# 20240610.net
KiCad netlist of a schematic drawn in EAGLE
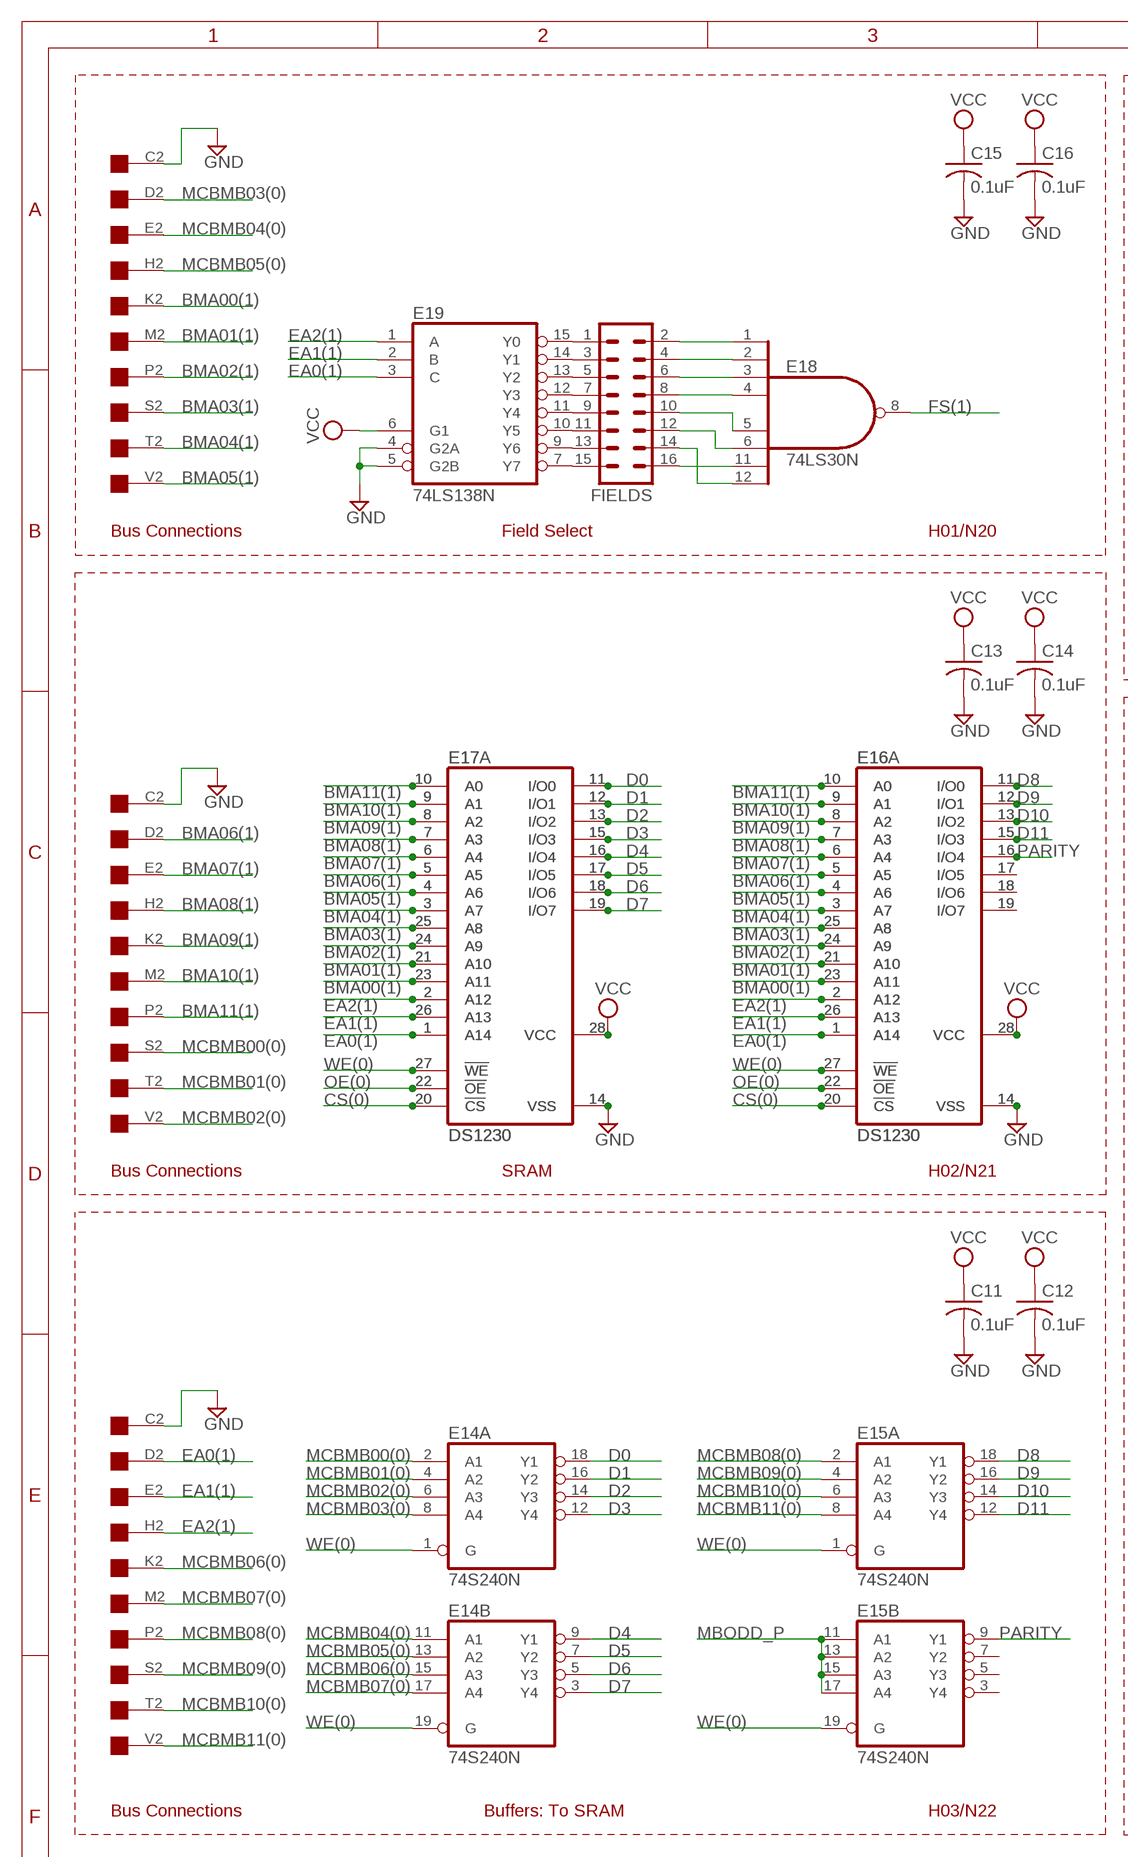
[diagram p0: schematic, sheet 1, part 1 of 2]
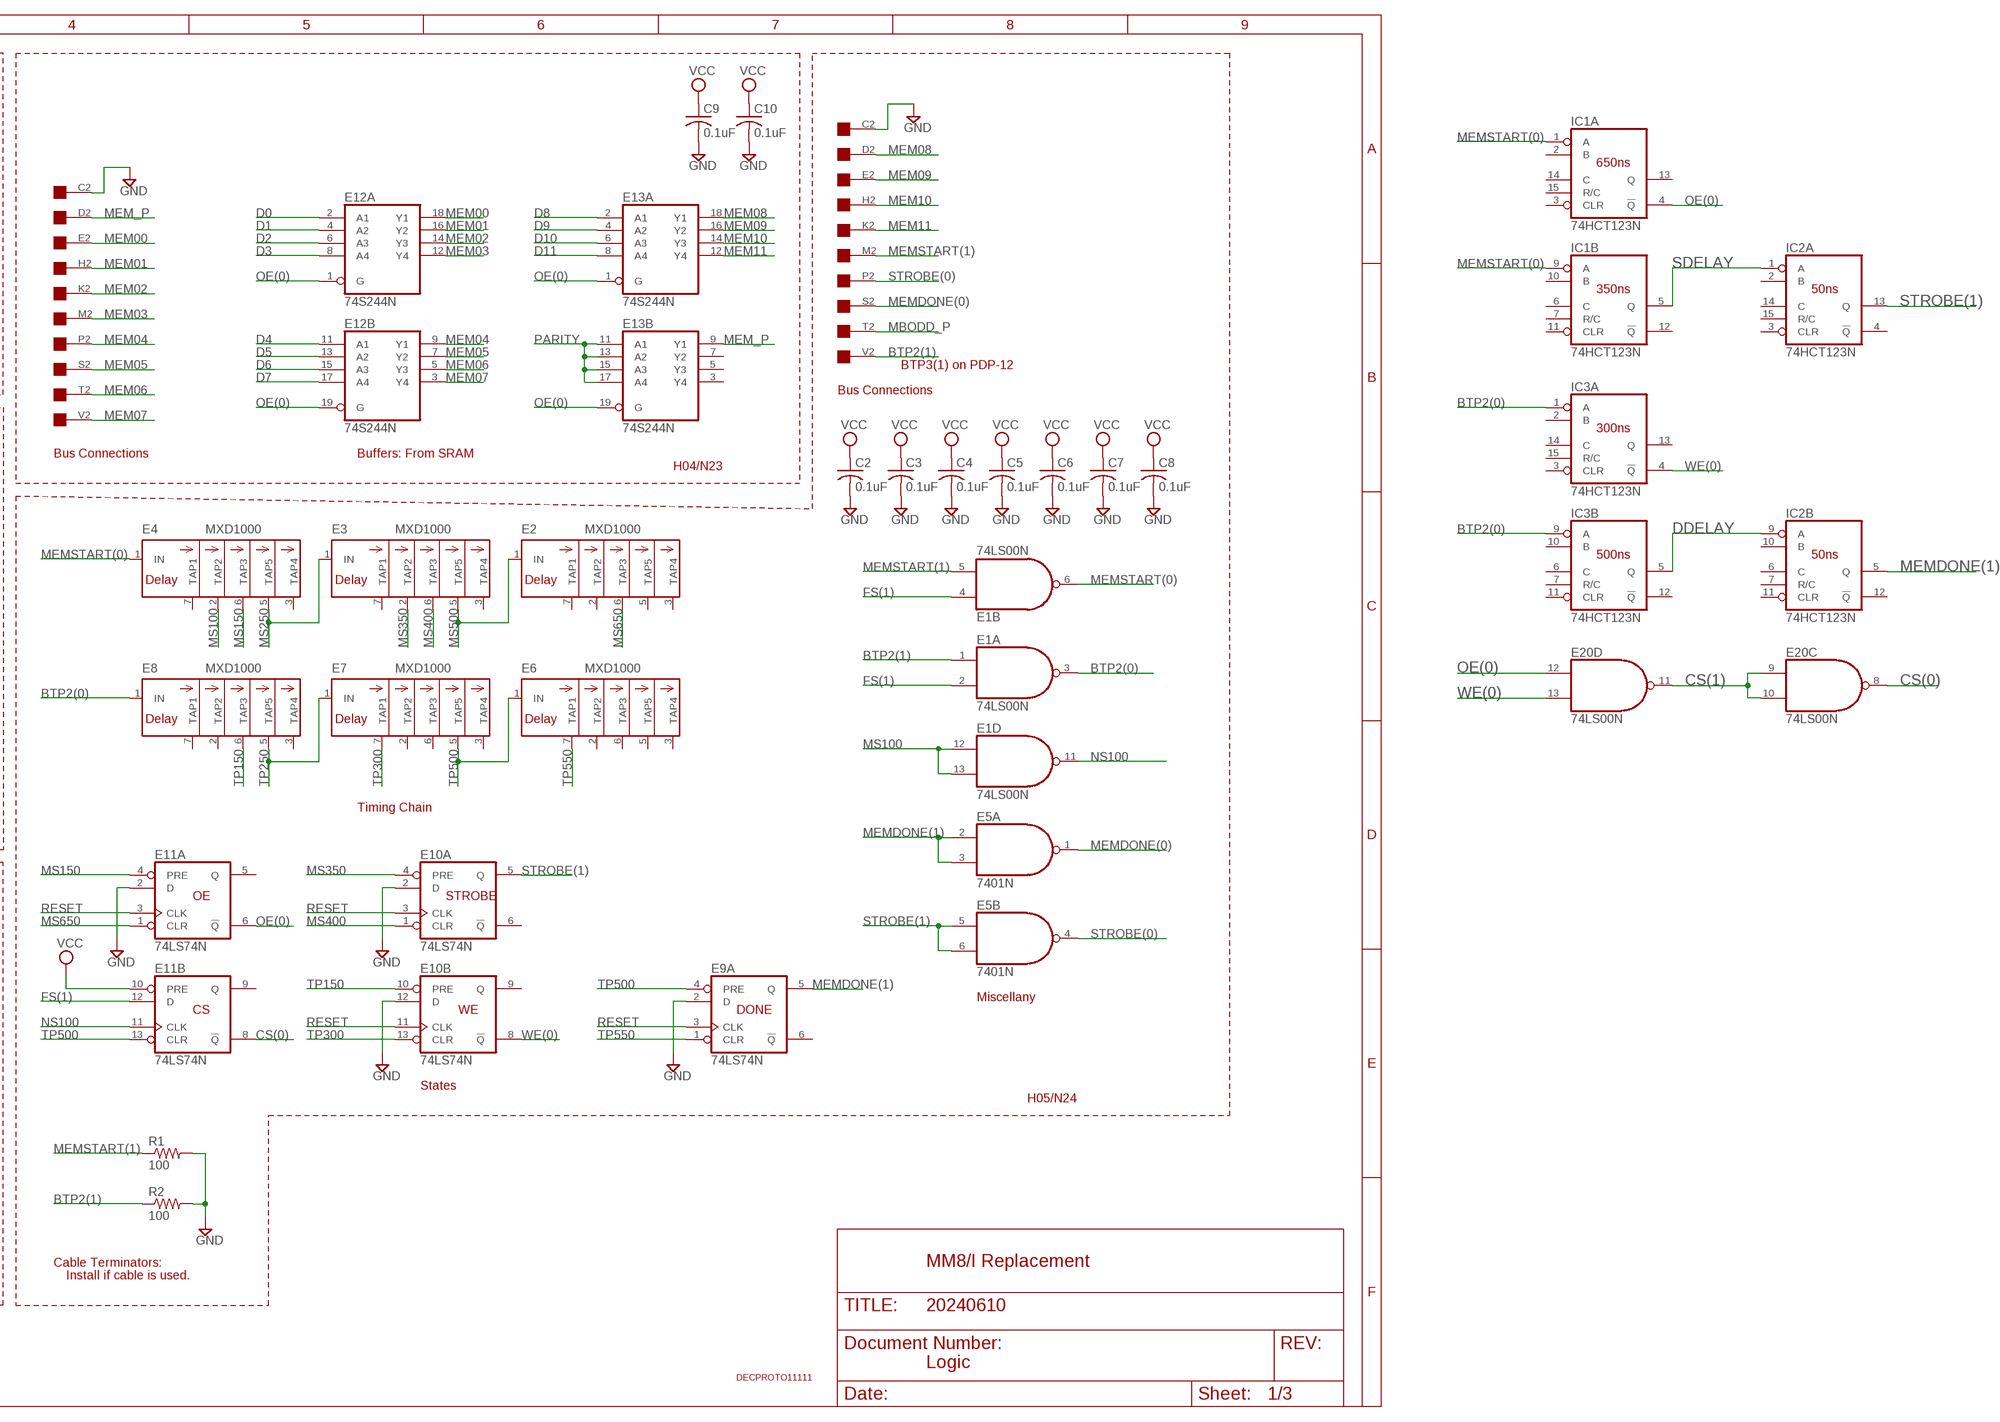
[diagram p1: schematic, sheet 1, part 2 of 2]
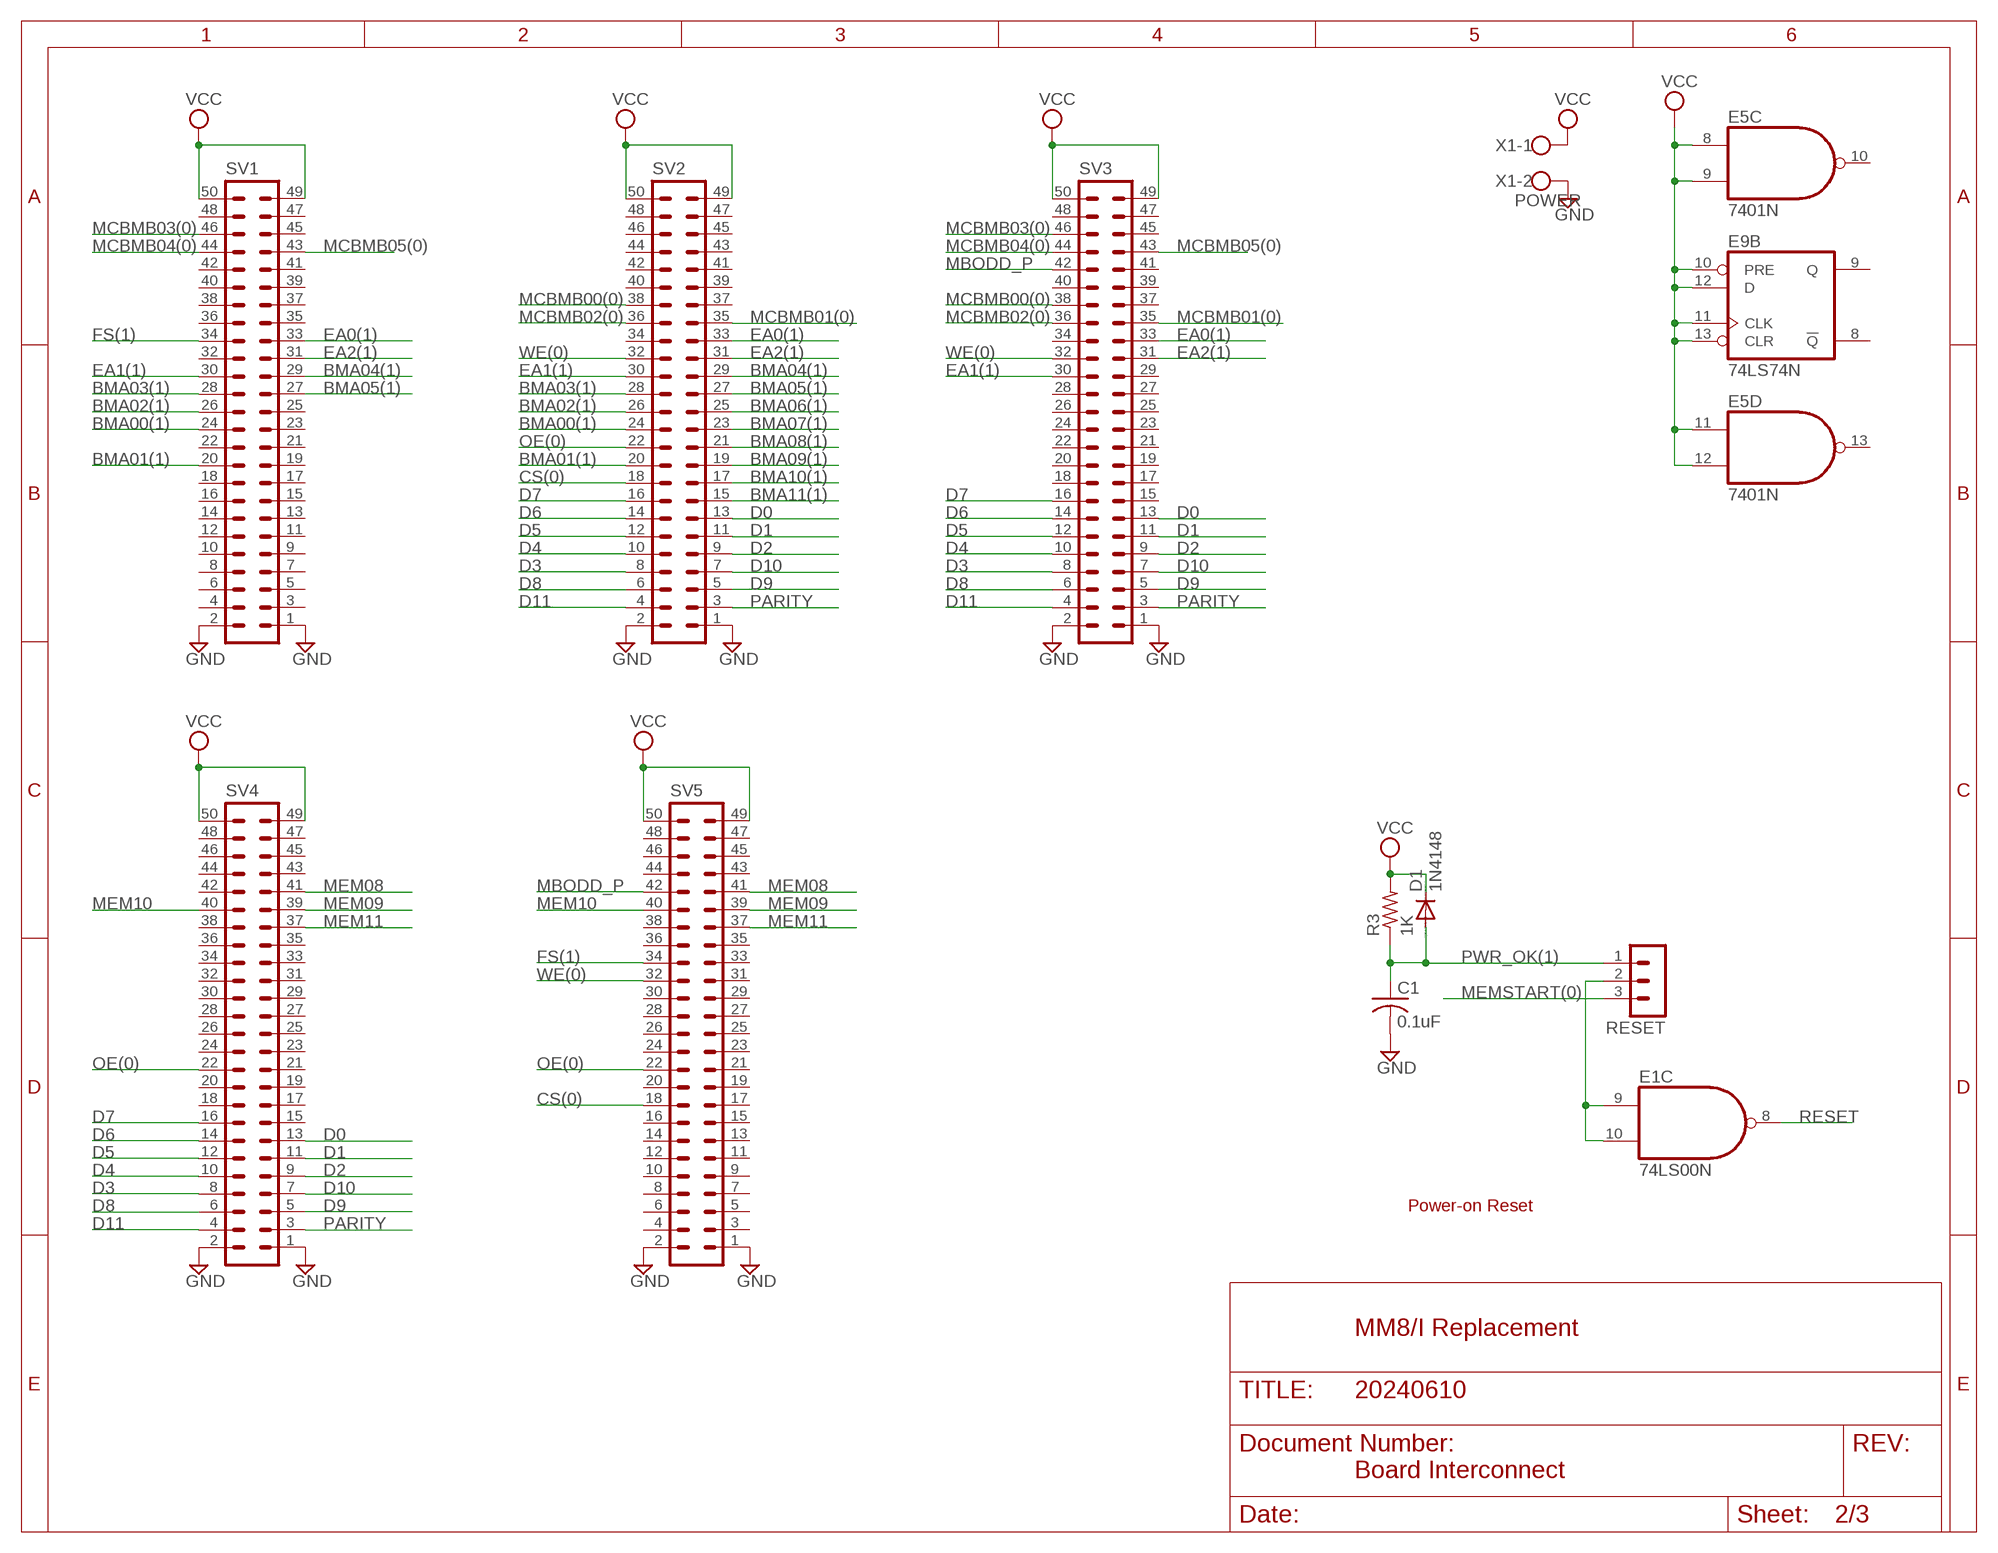
[diagram p2: schematic, sheet 2]
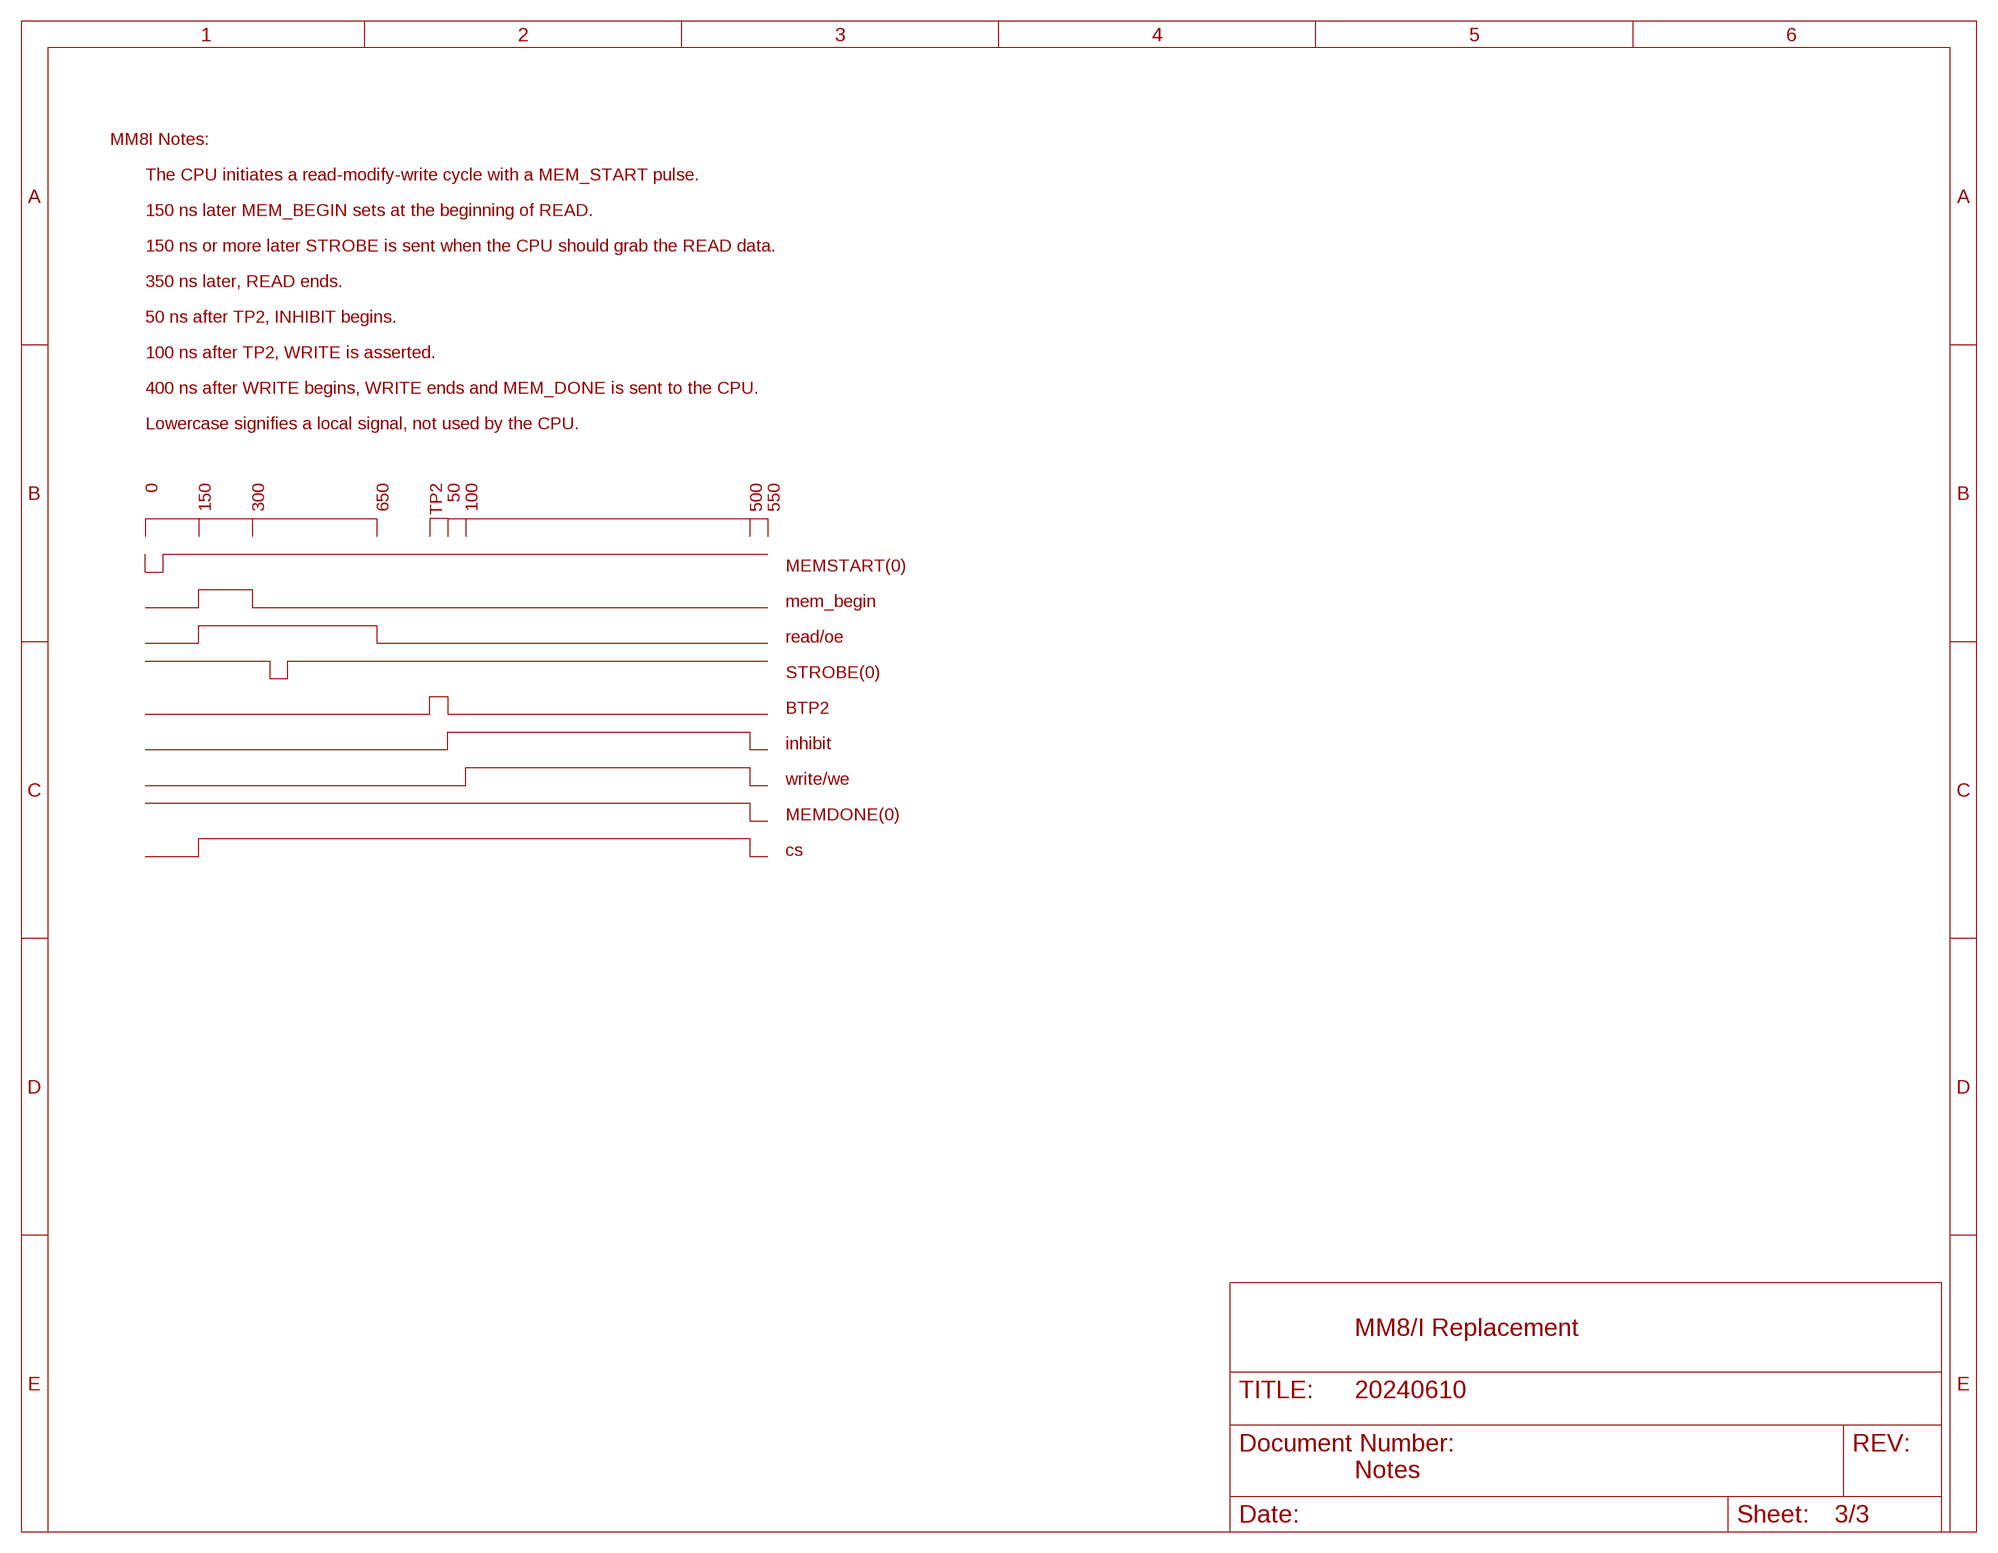
[diagram p3: schematic, sheet 3]

(export (version "E")
  (design (tool "Eeschema 10.0.6"))
  (components
    (comp (ref "C1")
      (value "0.1uF")
      (footprint "eagle-import:C050-025X075")
      (libsource (lib "eagle-import") (part "C-US050-025X075"))
    )
    (comp (ref "D1")
      (value "1N4148")
      (footprint "eagle-import:DO35-10")
      (libsource (lib "eagle-import") (part "1N4148DO35-10"))
    )
    (comp (ref "E1")
      (value "74LS00N")
      (footprint "eagle-import:DIL14")
      (libsource (lib "eagle-import") (part "7400NLS"))
    )
    (comp (ref "E5")
      (value "7401N")
      (footprint "eagle-import:DIL14")
      (libsource (lib "eagle-import") (part "7401NLS"))
    )
    (comp (ref "E9")
      (value "74LS74N")
      (footprint "eagle-import:DIL14")
      (libsource (lib "eagle-import") (part "7474NLS"))
    )
    (comp (ref "R3")
      (value "1K")
      (footprint "eagle-import:0207_10")
      (libsource (lib "eagle-import") (part "R-US_0207/10"))
    )
    (comp (ref "RESET")
      (value "MA03-1")
      (footprint "eagle-import:MA03-1")
      (libsource (lib "eagle-import") (part "MA03-1"))
    )
    (comp (ref "SV1")
      (value "ML50L")
      (footprint "eagle-import:ML50L")
      (libsource (lib "eagle-import") (part "ML50L"))
    )
    (comp (ref "SV2")
      (value "ML50L")
      (footprint "eagle-import:ML50L")
      (libsource (lib "eagle-import") (part "ML50L"))
    )
    (comp (ref "SV3")
      (value "ML50L")
      (footprint "eagle-import:ML50L")
      (libsource (lib "eagle-import") (part "ML50L"))
    )
    (comp (ref "SV4")
      (value "ML50L")
      (footprint "eagle-import:ML50L")
      (libsource (lib "eagle-import") (part "ML50L"))
    )
    (comp (ref "SV5")
      (value "ML50L")
      (footprint "eagle-import:ML50L")
      (libsource (lib "eagle-import") (part "ML50L"))
    )
    (comp (ref "X1")
      (value "POWER")
      (footprint "eagle-import:W237-102")
      (fields (field (name "MPN") "237-102"))
      (libsource (lib "eagle-import") (part "W237-102"))
    )
    (comp (ref "C2")
      (value "0.1uF")
      (footprint "eagle-import:C050-025X075")
      (libsource (lib "eagle-import") (part "C-US050-025X075"))
    )
    (comp (ref "C3")
      (value "0.1uF")
      (footprint "eagle-import:C050-025X075")
      (libsource (lib "eagle-import") (part "C-US050-025X075"))
    )
    (comp (ref "C4")
      (value "0.1uF")
      (footprint "eagle-import:C050-025X075")
      (libsource (lib "eagle-import") (part "C-US050-025X075"))
    )
    (comp (ref "C5")
      (value "0.1uF")
      (footprint "eagle-import:C050-025X075")
      (libsource (lib "eagle-import") (part "C-US050-025X075"))
    )
    (comp (ref "C6")
      (value "0.1uF")
      (footprint "eagle-import:C050-025X075")
      (libsource (lib "eagle-import") (part "C-US050-025X075"))
    )
    (comp (ref "C7")
      (value "0.1uF")
      (footprint "eagle-import:C050-025X075")
      (libsource (lib "eagle-import") (part "C-US050-025X075"))
    )
    (comp (ref "C8")
      (value "0.1uF")
      (footprint "eagle-import:C050-025X075")
      (libsource (lib "eagle-import") (part "C-US050-025X075"))
    )
    (comp (ref "C9")
      (value "0.1uF")
      (footprint "eagle-import:C050-025X075")
      (libsource (lib "eagle-import") (part "C-US050-025X075"))
    )
    (comp (ref "C10")
      (value "0.1uF")
      (footprint "eagle-import:C050-025X075")
      (libsource (lib "eagle-import") (part "C-US050-025X075"))
    )
    (comp (ref "C11")
      (value "0.1uF")
      (footprint "eagle-import:C050-025X075")
      (libsource (lib "eagle-import") (part "C-US050-025X075"))
    )
    (comp (ref "C12")
      (value "0.1uF")
      (footprint "eagle-import:C050-025X075")
      (libsource (lib "eagle-import") (part "C-US050-025X075"))
    )
    (comp (ref "C13")
      (value "0.1uF")
      (footprint "eagle-import:C050-025X075")
      (libsource (lib "eagle-import") (part "C-US050-025X075"))
    )
    (comp (ref "C14")
      (value "0.1uF")
      (footprint "eagle-import:C050-025X075")
      (libsource (lib "eagle-import") (part "C-US050-025X075"))
    )
    (comp (ref "C15")
      (value "0.1uF")
      (footprint "eagle-import:C050-025X075")
      (libsource (lib "eagle-import") (part "C-US050-025X075"))
    )
    (comp (ref "C16")
      (value "0.1uF")
      (footprint "eagle-import:C050-025X075")
      (libsource (lib "eagle-import") (part "C-US050-025X075"))
    )
    (comp (ref "E2")
      (value "MXD1000")
      (footprint "eagle-import:DIL08")
      (libsource (lib "eagle-import") (part "MXD1000"))
    )
    (comp (ref "E3")
      (value "MXD1000")
      (footprint "eagle-import:DIL08")
      (libsource (lib "eagle-import") (part "MXD1000"))
    )
    (comp (ref "E4")
      (value "MXD1000")
      (footprint "eagle-import:DIL08")
      (libsource (lib "eagle-import") (part "MXD1000"))
    )
    (comp (ref "E6")
      (value "MXD1000")
      (footprint "eagle-import:DIL08")
      (libsource (lib "eagle-import") (part "MXD1000"))
    )
    (comp (ref "E7")
      (value "MXD1000")
      (footprint "eagle-import:DIL08")
      (libsource (lib "eagle-import") (part "MXD1000"))
    )
    (comp (ref "E8")
      (value "MXD1000")
      (footprint "eagle-import:DIL08")
      (libsource (lib "eagle-import") (part "MXD1000"))
    )
    (comp (ref "E10")
      (value "74LS74N")
      (footprint "eagle-import:DIL14")
      (libsource (lib "eagle-import") (part "7474NLS"))
    )
    (comp (ref "E11")
      (value "74LS74N")
      (footprint "eagle-import:DIL14")
      (libsource (lib "eagle-import") (part "7474NLS"))
    )
    (comp (ref "E12")
      (value "74S244N")
      (footprint "eagle-import:DIL20")
      (libsource (lib "eagle-import") (part "74244NS"))
    )
    (comp (ref "E13")
      (value "74S244N")
      (footprint "eagle-import:DIL20")
      (libsource (lib "eagle-import") (part "74244NS"))
    )
    (comp (ref "E14")
      (value "74S240N")
      (footprint "eagle-import:DIL20")
      (libsource (lib "eagle-import") (part "74240NS"))
    )
    (comp (ref "E15")
      (value "74S240N")
      (footprint "eagle-import:DIL20")
      (libsource (lib "eagle-import") (part "74240NS"))
    )
    (comp (ref "E16")
      (value "DS1230")
      (footprint "eagle-import:DIL28-6")
      (libsource (lib "eagle-import") (part "62256P"))
    )
    (comp (ref "E16A")
      (value "DS1230")
      (footprint "eagle-import:DIL28-3")
      (libsource (lib "eagle-import") (part "62832P"))
    )
    (comp (ref "E17")
      (value "DS1230")
      (footprint "eagle-import:DIL28-6")
      (libsource (lib "eagle-import") (part "62256P"))
    )
    (comp (ref "E17A")
      (value "DS1230")
      (footprint "eagle-import:DIL28-3")
      (libsource (lib "eagle-import") (part "62832P"))
    )
    (comp (ref "E18")
      (value "74LS30N")
      (footprint "eagle-import:DIL14")
      (libsource (lib "eagle-import") (part "7430NLS"))
    )
    (comp (ref "E19")
      (value "74LS138N")
      (footprint "eagle-import:DIL16")
      (libsource (lib "eagle-import") (part "74138NLS"))
    )
    (comp (ref "E20")
      (value "74LS00N")
      (footprint "eagle-import:DIL14")
      (libsource (lib "eagle-import") (part "7400NLS"))
    )
    (comp (ref "FIELDS")
      (value "MA08-2")
      (footprint "eagle-import:MA08-2")
      (libsource (lib "eagle-import") (part "MA08-2"))
    )
    (comp (ref "H01")
      (value "EDGE-1")
      (footprint "eagle-import:EDGE-CON1")
      (libsource (lib "eagle-import") (part "EDGE-1"))
    )
    (comp (ref "H02")
      (value "EDGE-1")
      (footprint "eagle-import:EDGE-CON1")
      (libsource (lib "eagle-import") (part "EDGE-1"))
    )
    (comp (ref "H03")
      (value "EDGE-1")
      (footprint "eagle-import:EDGE-CON1")
      (libsource (lib "eagle-import") (part "EDGE-1"))
    )
    (comp (ref "H04")
      (value "EDGE-1")
      (footprint "eagle-import:EDGE-CON1")
      (libsource (lib "eagle-import") (part "EDGE-1"))
    )
    (comp (ref "H05")
      (value "EDGE-1")
      (footprint "eagle-import:EDGE-CON1")
      (libsource (lib "eagle-import") (part "EDGE-1"))
    )
    (comp (ref "IC1")
      (value "74HCT123N")
      (footprint "eagle-import:DIL16")
      (libsource (lib "eagle-import") (part "74123NLS"))
    )
    (comp (ref "IC2")
      (value "74HCT123N")
      (footprint "eagle-import:DIL16")
      (libsource (lib "eagle-import") (part "74123NLS"))
    )
    (comp (ref "IC3")
      (value "74HCT123N")
      (footprint "eagle-import:DIL16")
      (libsource (lib "eagle-import") (part "74123NLS"))
    )
    (comp (ref "R1")
      (value "100")
      (footprint "eagle-import:0207_10")
      (libsource (lib "eagle-import") (part "R-US_0207/10"))
    )
    (comp (ref "R2")
      (value "100")
      (footprint "eagle-import:0207_10")
      (libsource (lib "eagle-import") (part "R-US_0207/10"))
    )
    (comp (ref "U$6")
      (value "DECPROTO11111")
      (footprint "eagle-import:DECPROTO11111")
      (libsource (lib "eagle-import") (part "DECPROTO11111"))
    )
  )
  (nets
    (net (code "1") (name "BMA00(1)") (class "Default")
      (node (ref "E16") (pin "23") (pinfunction "A11_23") (pintype "input"))
      (node (ref "E16A") (pin "23") (pinfunction "A11_23") (pintype "input"))
      (node (ref "E17") (pin "23") (pinfunction "A11_23") (pintype "input"))
      (node (ref "E17A") (pin "23") (pinfunction "A11_23") (pintype "input"))
      (node (ref "H01") (pin "K2") (pinfunction "1_K2") (pintype "bidirectional"))
      (node (ref "SV1") (pin "24") (pinfunction "24_24") (pintype "passive"))
      (node (ref "SV2") (pin "24") (pinfunction "24_24") (pintype "passive"))
    )
    (net (code "2") (name "BMA01(1)") (class "Default")
      (node (ref "E16") (pin "21") (pinfunction "A10_21") (pintype "input"))
      (node (ref "E16A") (pin "21") (pinfunction "A10_21") (pintype "input"))
      (node (ref "E17") (pin "21") (pinfunction "A10_21") (pintype "input"))
      (node (ref "E17A") (pin "21") (pinfunction "A10_21") (pintype "input"))
      (node (ref "H01") (pin "M2") (pinfunction "1_M2") (pintype "bidirectional"))
      (node (ref "SV1") (pin "20") (pinfunction "20_20") (pintype "passive"))
      (node (ref "SV2") (pin "20") (pinfunction "20_20") (pintype "passive"))
    )
    (net (code "3") (name "BMA02(1)") (class "Default")
      (node (ref "E16") (pin "24") (pinfunction "A9_24") (pintype "input"))
      (node (ref "E16A") (pin "24") (pinfunction "A9_24") (pintype "input"))
      (node (ref "E17") (pin "24") (pinfunction "A9_24") (pintype "input"))
      (node (ref "E17A") (pin "24") (pinfunction "A9_24") (pintype "input"))
      (node (ref "H01") (pin "P2") (pinfunction "1_P2") (pintype "bidirectional"))
      (node (ref "SV1") (pin "26") (pinfunction "26_26") (pintype "passive"))
      (node (ref "SV2") (pin "26") (pinfunction "26_26") (pintype "passive"))
    )
    (net (code "4") (name "BMA03(1)") (class "Default")
      (node (ref "E16") (pin "25") (pinfunction "A8_25") (pintype "input"))
      (node (ref "E16A") (pin "25") (pinfunction "A8_25") (pintype "input"))
      (node (ref "E17") (pin "25") (pinfunction "A8_25") (pintype "input"))
      (node (ref "E17A") (pin "25") (pinfunction "A8_25") (pintype "input"))
      (node (ref "H01") (pin "S2") (pinfunction "1_S2") (pintype "bidirectional"))
      (node (ref "SV1") (pin "28") (pinfunction "28_28") (pintype "passive"))
      (node (ref "SV2") (pin "28") (pinfunction "28_28") (pintype "passive"))
    )
    (net (code "5") (name "BMA04(1)") (class "Default")
      (node (ref "E16") (pin "3") (pinfunction "A7_3") (pintype "input"))
      (node (ref "E16A") (pin "3") (pinfunction "A7_3") (pintype "input"))
      (node (ref "E17") (pin "3") (pinfunction "A7_3") (pintype "input"))
      (node (ref "E17A") (pin "3") (pinfunction "A7_3") (pintype "input"))
      (node (ref "H01") (pin "T2") (pinfunction "1_T2") (pintype "bidirectional"))
      (node (ref "SV1") (pin "29") (pinfunction "29_29") (pintype "passive"))
      (node (ref "SV2") (pin "29") (pinfunction "29_29") (pintype "passive"))
    )
    (net (code "6") (name "BMA05(1)") (class "Default")
      (node (ref "E16") (pin "4") (pinfunction "A6_4") (pintype "input"))
      (node (ref "E16A") (pin "4") (pinfunction "A6_4") (pintype "input"))
      (node (ref "E17") (pin "4") (pinfunction "A6_4") (pintype "input"))
      (node (ref "E17A") (pin "4") (pinfunction "A6_4") (pintype "input"))
      (node (ref "H01") (pin "V2") (pinfunction "1_V2") (pintype "bidirectional"))
      (node (ref "SV1") (pin "27") (pinfunction "27_27") (pintype "passive"))
      (node (ref "SV2") (pin "27") (pinfunction "27_27") (pintype "passive"))
    )
    (net (code "7") (name "BMA06(1)") (class "Default")
      (node (ref "E16") (pin "5") (pinfunction "A5_5") (pintype "input"))
      (node (ref "E16A") (pin "5") (pinfunction "A5_5") (pintype "input"))
      (node (ref "E17") (pin "5") (pinfunction "A5_5") (pintype "input"))
      (node (ref "E17A") (pin "5") (pinfunction "A5_5") (pintype "input"))
      (node (ref "H02") (pin "D2") (pinfunction "1_D2") (pintype "bidirectional"))
      (node (ref "SV2") (pin "25") (pinfunction "25_25") (pintype "passive"))
    )
    (net (code "8") (name "BMA07(1)") (class "Default")
      (node (ref "E16") (pin "6") (pinfunction "A4_6") (pintype "input"))
      (node (ref "E16A") (pin "6") (pinfunction "A4_6") (pintype "input"))
      (node (ref "E17") (pin "6") (pinfunction "A4_6") (pintype "input"))
      (node (ref "E17A") (pin "6") (pinfunction "A4_6") (pintype "input"))
      (node (ref "H02") (pin "E2") (pinfunction "1_E2") (pintype "bidirectional"))
      (node (ref "SV2") (pin "23") (pinfunction "23_23") (pintype "passive"))
    )
    (net (code "9") (name "BMA08(1)") (class "Default")
      (node (ref "E16") (pin "7") (pinfunction "A3_7") (pintype "input"))
      (node (ref "E16A") (pin "7") (pinfunction "A3_7") (pintype "input"))
      (node (ref "E17") (pin "7") (pinfunction "A3_7") (pintype "input"))
      (node (ref "E17A") (pin "7") (pinfunction "A3_7") (pintype "input"))
      (node (ref "H02") (pin "H2") (pinfunction "1_H2") (pintype "bidirectional"))
      (node (ref "SV2") (pin "21") (pinfunction "21_21") (pintype "passive"))
    )
    (net (code "10") (name "BMA09(1)") (class "Default")
      (node (ref "E16") (pin "8") (pinfunction "A2_8") (pintype "input"))
      (node (ref "E16A") (pin "8") (pinfunction "A2_8") (pintype "input"))
      (node (ref "E17") (pin "8") (pinfunction "A2_8") (pintype "input"))
      (node (ref "E17A") (pin "8") (pinfunction "A2_8") (pintype "input"))
      (node (ref "H02") (pin "K2") (pinfunction "1_K2") (pintype "bidirectional"))
      (node (ref "SV2") (pin "19") (pinfunction "19_19") (pintype "passive"))
    )
    (net (code "11") (name "BMA10(1)") (class "Default")
      (node (ref "E16") (pin "9") (pinfunction "A1_9") (pintype "input"))
      (node (ref "E16A") (pin "9") (pinfunction "A1_9") (pintype "input"))
      (node (ref "E17") (pin "9") (pinfunction "A1_9") (pintype "input"))
      (node (ref "E17A") (pin "9") (pinfunction "A1_9") (pintype "input"))
      (node (ref "H02") (pin "M2") (pinfunction "1_M2") (pintype "bidirectional"))
      (node (ref "SV2") (pin "17") (pinfunction "17_17") (pintype "passive"))
    )
    (net (code "12") (name "BMA11(1)") (class "Default")
      (node (ref "E16") (pin "10") (pinfunction "A0_10") (pintype "input"))
      (node (ref "E16A") (pin "10") (pinfunction "A0_10") (pintype "input"))
      (node (ref "E17") (pin "10") (pinfunction "A0_10") (pintype "input"))
      (node (ref "E17A") (pin "10") (pinfunction "A0_10") (pintype "input"))
      (node (ref "H02") (pin "P2") (pinfunction "1_P2") (pintype "bidirectional"))
      (node (ref "SV2") (pin "15") (pinfunction "15_15") (pintype "passive"))
    )
    (net (code "13") (name "BTP2(0)") (class "Default")
      (node (ref "E1") (pin "3") (pinfunction "O_3") (pintype "output"))
      (node (ref "E8") (pin "1") (pinfunction "IN_1") (pintype "input"))
      (node (ref "IC3") (pin "1") (pinfunction "A_1") (pintype "input"))
      (node (ref "IC3") (pin "9") (pinfunction "A_9") (pintype "input"))
    )
    (net (code "14") (name "BTP2(1)") (class "Default")
      (node (ref "E1") (pin "1") (pinfunction "I0_1") (pintype "input"))
      (node (ref "H05") (pin "V2") (pinfunction "1_V2") (pintype "bidirectional"))
      (node (ref "R2") (pin "1") (pinfunction "1_1") (pintype "passive"))
    )
    (net (code "15") (name "CS(0)") (class "Default")
      (node (ref "E11") (pin "8") (pinfunction "~{Q}_8") (pintype "output"))
      (node (ref "E16") (pin "20") (pinfunction "~{CS}_20") (pintype "input"))
      (node (ref "E16A") (pin "20") (pinfunction "~{CS}_20") (pintype "input"))
      (node (ref "E17") (pin "20") (pinfunction "~{CS}_20") (pintype "input"))
      (node (ref "E17A") (pin "20") (pinfunction "~{CS}_20") (pintype "input"))
      (node (ref "E20") (pin "8") (pinfunction "O_8") (pintype "output"))
      (node (ref "SV2") (pin "18") (pinfunction "18_18") (pintype "passive"))
      (node (ref "SV5") (pin "18") (pinfunction "18_18") (pintype "passive"))
    )
    (net (code "16") (name "CS(1)") (class "Default")
      (node (ref "E20") (pin "10") (pinfunction "I1_10") (pintype "input"))
      (node (ref "E20") (pin "11") (pinfunction "O_11") (pintype "output"))
      (node (ref "E20") (pin "9") (pinfunction "I0_9") (pintype "input"))
    )
    (net (code "17") (name "D0") (class "Default")
      (node (ref "E12") (pin "2") (pinfunction "A1_2") (pintype "input"))
      (node (ref "E14") (pin "18") (pinfunction "Y1_18") (pintype "tri_state"))
      (node (ref "E17") (pin "11") (pinfunction "I/O0_11") (pintype "bidirectional"))
      (node (ref "E17A") (pin "11") (pinfunction "I/O0_11") (pintype "bidirectional"))
      (node (ref "SV2") (pin "13") (pinfunction "13_13") (pintype "passive"))
      (node (ref "SV3") (pin "13") (pinfunction "13_13") (pintype "passive"))
      (node (ref "SV4") (pin "13") (pinfunction "13_13") (pintype "passive"))
    )
    (net (code "18") (name "D1") (class "Default")
      (node (ref "E12") (pin "4") (pinfunction "A2_4") (pintype "input"))
      (node (ref "E14") (pin "16") (pinfunction "Y2_16") (pintype "tri_state"))
      (node (ref "E17") (pin "12") (pinfunction "I/O1_12") (pintype "bidirectional"))
      (node (ref "E17A") (pin "12") (pinfunction "I/O1_12") (pintype "bidirectional"))
      (node (ref "SV2") (pin "11") (pinfunction "11_11") (pintype "passive"))
      (node (ref "SV3") (pin "11") (pinfunction "11_11") (pintype "passive"))
      (node (ref "SV4") (pin "11") (pinfunction "11_11") (pintype "passive"))
    )
    (net (code "19") (name "D2") (class "Default")
      (node (ref "E12") (pin "6") (pinfunction "A3_6") (pintype "input"))
      (node (ref "E14") (pin "14") (pinfunction "Y3_14") (pintype "tri_state"))
      (node (ref "E17") (pin "13") (pinfunction "I/O2_13") (pintype "bidirectional"))
      (node (ref "E17A") (pin "13") (pinfunction "I/O2_13") (pintype "bidirectional"))
      (node (ref "SV2") (pin "9") (pinfunction "9_9") (pintype "passive"))
      (node (ref "SV3") (pin "9") (pinfunction "9_9") (pintype "passive"))
      (node (ref "SV4") (pin "9") (pinfunction "9_9") (pintype "passive"))
    )
    (net (code "20") (name "D3") (class "Default")
      (node (ref "E12") (pin "8") (pinfunction "A4_8") (pintype "input"))
      (node (ref "E14") (pin "12") (pinfunction "Y4_12") (pintype "tri_state"))
      (node (ref "E17") (pin "15") (pinfunction "I/O3_15") (pintype "bidirectional"))
      (node (ref "E17A") (pin "15") (pinfunction "I/O3_15") (pintype "bidirectional"))
      (node (ref "SV2") (pin "8") (pinfunction "8_8") (pintype "passive"))
      (node (ref "SV3") (pin "8") (pinfunction "8_8") (pintype "passive"))
      (node (ref "SV4") (pin "8") (pinfunction "8_8") (pintype "passive"))
    )
    (net (code "21") (name "D4") (class "Default")
      (node (ref "E12") (pin "11") (pinfunction "A1_11") (pintype "input"))
      (node (ref "E14") (pin "9") (pinfunction "Y1_9") (pintype "tri_state"))
      (node (ref "E17") (pin "16") (pinfunction "I/O4_16") (pintype "bidirectional"))
      (node (ref "E17A") (pin "16") (pinfunction "I/O4_16") (pintype "bidirectional"))
      (node (ref "SV2") (pin "10") (pinfunction "10_10") (pintype "passive"))
      (node (ref "SV3") (pin "10") (pinfunction "10_10") (pintype "passive"))
      (node (ref "SV4") (pin "10") (pinfunction "10_10") (pintype "passive"))
    )
    (net (code "22") (name "D5") (class "Default")
      (node (ref "E12") (pin "13") (pinfunction "A2_13") (pintype "input"))
      (node (ref "E14") (pin "7") (pinfunction "Y2_7") (pintype "tri_state"))
      (node (ref "E17") (pin "17") (pinfunction "I/O5_17") (pintype "bidirectional"))
      (node (ref "E17A") (pin "17") (pinfunction "I/O5_17") (pintype "bidirectional"))
      (node (ref "SV2") (pin "12") (pinfunction "12_12") (pintype "passive"))
      (node (ref "SV3") (pin "12") (pinfunction "12_12") (pintype "passive"))
      (node (ref "SV4") (pin "12") (pinfunction "12_12") (pintype "passive"))
    )
    (net (code "23") (name "D6") (class "Default")
      (node (ref "E12") (pin "15") (pinfunction "A3_15") (pintype "input"))
      (node (ref "E14") (pin "5") (pinfunction "Y3_5") (pintype "tri_state"))
      (node (ref "E17") (pin "18") (pinfunction "I/O6_18") (pintype "bidirectional"))
      (node (ref "E17A") (pin "18") (pinfunction "I/O6_18") (pintype "bidirectional"))
      (node (ref "SV2") (pin "14") (pinfunction "14_14") (pintype "passive"))
      (node (ref "SV3") (pin "14") (pinfunction "14_14") (pintype "passive"))
      (node (ref "SV4") (pin "14") (pinfunction "14_14") (pintype "passive"))
    )
    (net (code "24") (name "D7") (class "Default")
      (node (ref "E12") (pin "17") (pinfunction "A4_17") (pintype "input"))
      (node (ref "E14") (pin "3") (pinfunction "Y4_3") (pintype "tri_state"))
      (node (ref "E17") (pin "19") (pinfunction "I/O7_19") (pintype "bidirectional"))
      (node (ref "E17A") (pin "19") (pinfunction "I/O7_19") (pintype "bidirectional"))
      (node (ref "SV2") (pin "16") (pinfunction "16_16") (pintype "passive"))
      (node (ref "SV3") (pin "16") (pinfunction "16_16") (pintype "passive"))
      (node (ref "SV4") (pin "16") (pinfunction "16_16") (pintype "passive"))
    )
    (net (code "25") (name "D8") (class "Default")
      (node (ref "E13") (pin "2") (pinfunction "A1_2") (pintype "input"))
      (node (ref "E15") (pin "18") (pinfunction "Y1_18") (pintype "tri_state"))
      (node (ref "E16") (pin "11") (pinfunction "I/O0_11") (pintype "bidirectional"))
      (node (ref "E16A") (pin "11") (pinfunction "I/O0_11") (pintype "bidirectional"))
      (node (ref "SV2") (pin "6") (pinfunction "6_6") (pintype "passive"))
      (node (ref "SV3") (pin "6") (pinfunction "6_6") (pintype "passive"))
      (node (ref "SV4") (pin "6") (pinfunction "6_6") (pintype "passive"))
    )
    (net (code "26") (name "D9") (class "Default")
      (node (ref "E13") (pin "4") (pinfunction "A2_4") (pintype "input"))
      (node (ref "E15") (pin "16") (pinfunction "Y2_16") (pintype "tri_state"))
      (node (ref "E16") (pin "12") (pinfunction "I/O1_12") (pintype "bidirectional"))
      (node (ref "E16A") (pin "12") (pinfunction "I/O1_12") (pintype "bidirectional"))
      (node (ref "SV2") (pin "5") (pinfunction "5_5") (pintype "passive"))
      (node (ref "SV3") (pin "5") (pinfunction "5_5") (pintype "passive"))
      (node (ref "SV4") (pin "5") (pinfunction "5_5") (pintype "passive"))
    )
    (net (code "27") (name "D10") (class "Default")
      (node (ref "E13") (pin "6") (pinfunction "A3_6") (pintype "input"))
      (node (ref "E15") (pin "14") (pinfunction "Y3_14") (pintype "tri_state"))
      (node (ref "E16") (pin "13") (pinfunction "I/O2_13") (pintype "bidirectional"))
      (node (ref "E16A") (pin "13") (pinfunction "I/O2_13") (pintype "bidirectional"))
      (node (ref "SV2") (pin "7") (pinfunction "7_7") (pintype "passive"))
      (node (ref "SV3") (pin "7") (pinfunction "7_7") (pintype "passive"))
      (node (ref "SV4") (pin "7") (pinfunction "7_7") (pintype "passive"))
    )
    (net (code "28") (name "D11") (class "Default")
      (node (ref "E13") (pin "8") (pinfunction "A4_8") (pintype "input"))
      (node (ref "E15") (pin "12") (pinfunction "Y4_12") (pintype "tri_state"))
      (node (ref "E16") (pin "15") (pinfunction "I/O3_15") (pintype "bidirectional"))
      (node (ref "E16A") (pin "15") (pinfunction "I/O3_15") (pintype "bidirectional"))
      (node (ref "SV2") (pin "4") (pinfunction "4_4") (pintype "passive"))
      (node (ref "SV3") (pin "4") (pinfunction "4_4") (pintype "passive"))
      (node (ref "SV4") (pin "4") (pinfunction "4_4") (pintype "passive"))
    )
    (net (code "29") (name "DDELAY") (class "Default")
      (node (ref "IC2") (pin "9") (pinfunction "A_9") (pintype "input"))
      (node (ref "IC3") (pin "5") (pinfunction "Q_5") (pintype "output"))
    )
    (net (code "30") (name "EA0(1)") (class "Default")
      (node (ref "E16") (pin "1") (pinfunction "A14_1") (pintype "input"))
      (node (ref "E16A") (pin "1") (pinfunction "A14_1") (pintype "input"))
      (node (ref "E17") (pin "1") (pinfunction "A14_1") (pintype "input"))
      (node (ref "E17A") (pin "1") (pinfunction "A14_1") (pintype "input"))
      (node (ref "E19") (pin "3") (pinfunction "C_3") (pintype "input"))
      (node (ref "H03") (pin "D2") (pinfunction "1_D2") (pintype "bidirectional"))
      (node (ref "SV1") (pin "33") (pinfunction "33_33") (pintype "passive"))
      (node (ref "SV2") (pin "33") (pinfunction "33_33") (pintype "passive"))
      (node (ref "SV3") (pin "33") (pinfunction "33_33") (pintype "passive"))
    )
    (net (code "31") (name "EA1(1)") (class "Default")
      (node (ref "E16") (pin "26") (pinfunction "A13_26") (pintype "input"))
      (node (ref "E16A") (pin "26") (pinfunction "A13_26") (pintype "input"))
      (node (ref "E17") (pin "26") (pinfunction "A13_26") (pintype "input"))
      (node (ref "E17A") (pin "26") (pinfunction "A13_26") (pintype "input"))
      (node (ref "E19") (pin "2") (pinfunction "B_2") (pintype "input"))
      (node (ref "H03") (pin "E2") (pinfunction "1_E2") (pintype "bidirectional"))
      (node (ref "SV1") (pin "30") (pinfunction "30_30") (pintype "passive"))
      (node (ref "SV2") (pin "30") (pinfunction "30_30") (pintype "passive"))
      (node (ref "SV3") (pin "30") (pinfunction "30_30") (pintype "passive"))
    )
    (net (code "32") (name "EA2(1)") (class "Default")
      (node (ref "E16") (pin "2") (pinfunction "A12_2") (pintype "input"))
      (node (ref "E16A") (pin "2") (pinfunction "A12_2") (pintype "input"))
      (node (ref "E17") (pin "2") (pinfunction "A12_2") (pintype "input"))
      (node (ref "E17A") (pin "2") (pinfunction "A12_2") (pintype "input"))
      (node (ref "E19") (pin "1") (pinfunction "A_1") (pintype "input"))
      (node (ref "H03") (pin "H2") (pinfunction "1_H2") (pintype "bidirectional"))
      (node (ref "SV1") (pin "31") (pinfunction "31_31") (pintype "passive"))
      (node (ref "SV2") (pin "31") (pinfunction "31_31") (pintype "passive"))
      (node (ref "SV3") (pin "31") (pinfunction "31_31") (pintype "passive"))
    )
    (net (code "33") (name "FS(1)") (class "Default")
      (node (ref "E1") (pin "2") (pinfunction "I1_2") (pintype "input"))
      (node (ref "E1") (pin "4") (pinfunction "I0_4") (pintype "input"))
      (node (ref "E11") (pin "12") (pinfunction "D_12") (pintype "input"))
      (node (ref "E18") (pin "8") (pinfunction "O_8") (pintype "output"))
      (node (ref "SV1") (pin "34") (pinfunction "34_34") (pintype "passive"))
      (node (ref "SV5") (pin "34") (pinfunction "34_34") (pintype "passive"))
    )
    (net (code "34") (name "GND") (class "Default")
      (node (ref "C1") (pin "2") (pinfunction "2_2") (pintype "passive"))
      (node (ref "C10") (pin "2") (pinfunction "2_2") (pintype "passive"))
      (node (ref "C11") (pin "2") (pinfunction "2_2") (pintype "passive"))
      (node (ref "C12") (pin "2") (pinfunction "2_2") (pintype "passive"))
      (node (ref "C13") (pin "2") (pinfunction "2_2") (pintype "passive"))
      (node (ref "C14") (pin "2") (pinfunction "2_2") (pintype "passive"))
      (node (ref "C15") (pin "2") (pinfunction "2_2") (pintype "passive"))
      (node (ref "C16") (pin "2") (pinfunction "2_2") (pintype "passive"))
      (node (ref "C2") (pin "2") (pinfunction "2_2") (pintype "passive"))
      (node (ref "C3") (pin "2") (pinfunction "2_2") (pintype "passive"))
      (node (ref "C4") (pin "2") (pinfunction "2_2") (pintype "passive"))
      (node (ref "C5") (pin "2") (pinfunction "2_2") (pintype "passive"))
      (node (ref "C6") (pin "2") (pinfunction "2_2") (pintype "passive"))
      (node (ref "C7") (pin "2") (pinfunction "2_2") (pintype "passive"))
      (node (ref "C8") (pin "2") (pinfunction "2_2") (pintype "passive"))
      (node (ref "C9") (pin "2") (pinfunction "2_2") (pintype "passive"))
      (node (ref "E10") (pin "12") (pinfunction "D_12") (pintype "input"))
      (node (ref "E10") (pin "2") (pinfunction "D_2") (pintype "input"))
      (node (ref "E11") (pin "2") (pinfunction "D_2") (pintype "input"))
      (node (ref "E16") (pin "14") (pinfunction "VSS_14") (pintype "power_in"))
      (node (ref "E16A") (pin "14") (pinfunction "VSS_14") (pintype "power_in"))
      (node (ref "E17") (pin "14") (pinfunction "VSS_14") (pintype "power_in"))
      (node (ref "E17A") (pin "14") (pinfunction "VSS_14") (pintype "power_in"))
      (node (ref "E19") (pin "4") (pinfunction "G2A_4") (pintype "input"))
      (node (ref "E19") (pin "5") (pinfunction "G2B_5") (pintype "input"))
      (node (ref "E9") (pin "2") (pinfunction "D_2") (pintype "input"))
      (node (ref "H01") (pin "C2") (pinfunction "1_C2") (pintype "bidirectional"))
      (node (ref "H02") (pin "C2") (pinfunction "1_C2") (pintype "bidirectional"))
      (node (ref "H03") (pin "C2") (pinfunction "1_C2") (pintype "bidirectional"))
      (node (ref "H04") (pin "C2") (pinfunction "1_C2") (pintype "bidirectional"))
      (node (ref "H05") (pin "C2") (pinfunction "1_C2") (pintype "bidirectional"))
      (node (ref "R1") (pin "2") (pinfunction "2_2") (pintype "passive"))
      (node (ref "R2") (pin "2") (pinfunction "2_2") (pintype "passive"))
      (node (ref "SV1") (pin "1") (pinfunction "1_1") (pintype "passive"))
      (node (ref "SV1") (pin "2") (pinfunction "2_2") (pintype "passive"))
      (node (ref "SV2") (pin "1") (pinfunction "1_1") (pintype "passive"))
      (node (ref "SV2") (pin "2") (pinfunction "2_2") (pintype "passive"))
      (node (ref "SV3") (pin "1") (pinfunction "1_1") (pintype "passive"))
      (node (ref "SV3") (pin "2") (pinfunction "2_2") (pintype "passive"))
      (node (ref "SV4") (pin "1") (pinfunction "1_1") (pintype "passive"))
      (node (ref "SV4") (pin "2") (pinfunction "2_2") (pintype "passive"))
      (node (ref "SV5") (pin "1") (pinfunction "1_1") (pintype "passive"))
      (node (ref "SV5") (pin "2") (pinfunction "2_2") (pintype "passive"))
      (node (ref "X1") (pin "2") (pinfunction "KL_2") (pintype "passive"))
    )
    (net (code "35") (name "MBODD_P") (class "Default")
      (node (ref "E15") (pin "11") (pinfunction "A1_11") (pintype "input"))
      (node (ref "E15") (pin "13") (pinfunction "A2_13") (pintype "input"))
      (node (ref "E15") (pin "15") (pinfunction "A3_15") (pintype "input"))
      (node (ref "E15") (pin "17") (pinfunction "A4_17") (pintype "input"))
      (node (ref "H05") (pin "T2") (pinfunction "1_T2") (pintype "bidirectional"))
      (node (ref "SV3") (pin "42") (pinfunction "42_42") (pintype "passive"))
      (node (ref "SV5") (pin "42") (pinfunction "42_42") (pintype "passive"))
    )
    (net (code "36") (name "MCBMB00(0)") (class "Default")
      (node (ref "E14") (pin "2") (pinfunction "A1_2") (pintype "input"))
      (node (ref "H02") (pin "S2") (pinfunction "1_S2") (pintype "bidirectional"))
      (node (ref "SV2") (pin "38") (pinfunction "38_38") (pintype "passive"))
      (node (ref "SV3") (pin "38") (pinfunction "38_38") (pintype "passive"))
    )
    (net (code "37") (name "MCBMB01(0)") (class "Default")
      (node (ref "E14") (pin "4") (pinfunction "A2_4") (pintype "input"))
      (node (ref "H02") (pin "T2") (pinfunction "1_T2") (pintype "bidirectional"))
      (node (ref "SV2") (pin "35") (pinfunction "35_35") (pintype "passive"))
      (node (ref "SV3") (pin "35") (pinfunction "35_35") (pintype "passive"))
    )
    (net (code "38") (name "MCBMB02(0)") (class "Default")
      (node (ref "E14") (pin "6") (pinfunction "A3_6") (pintype "input"))
      (node (ref "H02") (pin "V2") (pinfunction "1_V2") (pintype "bidirectional"))
      (node (ref "SV2") (pin "36") (pinfunction "36_36") (pintype "passive"))
      (node (ref "SV3") (pin "36") (pinfunction "36_36") (pintype "passive"))
    )
    (net (code "39") (name "MCBMB03(0)") (class "Default")
      (node (ref "E14") (pin "8") (pinfunction "A4_8") (pintype "input"))
      (node (ref "H01") (pin "D2") (pinfunction "1_D2") (pintype "bidirectional"))
      (node (ref "SV1") (pin "46") (pinfunction "46_46") (pintype "passive"))
      (node (ref "SV3") (pin "46") (pinfunction "46_46") (pintype "passive"))
    )
    (net (code "40") (name "MCBMB04(0)") (class "Default")
      (node (ref "E14") (pin "11") (pinfunction "A1_11") (pintype "input"))
      (node (ref "H01") (pin "E2") (pinfunction "1_E2") (pintype "bidirectional"))
      (node (ref "SV1") (pin "44") (pinfunction "44_44") (pintype "passive"))
      (node (ref "SV3") (pin "44") (pinfunction "44_44") (pintype "passive"))
    )
    (net (code "41") (name "MCBMB05(0)") (class "Default")
      (node (ref "E14") (pin "13") (pinfunction "A2_13") (pintype "input"))
      (node (ref "H01") (pin "H2") (pinfunction "1_H2") (pintype "bidirectional"))
      (node (ref "SV1") (pin "43") (pinfunction "43_43") (pintype "passive"))
      (node (ref "SV3") (pin "43") (pinfunction "43_43") (pintype "passive"))
    )
    (net (code "42") (name "MCBMB06(0)") (class "Default")
      (node (ref "E14") (pin "15") (pinfunction "A3_15") (pintype "input"))
      (node (ref "H03") (pin "K2") (pinfunction "1_K2") (pintype "bidirectional"))
    )
    (net (code "43") (name "MCBMB07(0)") (class "Default")
      (node (ref "E14") (pin "17") (pinfunction "A4_17") (pintype "input"))
      (node (ref "H03") (pin "M2") (pinfunction "1_M2") (pintype "bidirectional"))
    )
    (net (code "44") (name "MCBMB08(0)") (class "Default")
      (node (ref "E15") (pin "2") (pinfunction "A1_2") (pintype "input"))
      (node (ref "H03") (pin "P2") (pinfunction "1_P2") (pintype "bidirectional"))
    )
    (net (code "45") (name "MCBMB09(0)") (class "Default")
      (node (ref "E15") (pin "4") (pinfunction "A2_4") (pintype "input"))
      (node (ref "H03") (pin "S2") (pinfunction "1_S2") (pintype "bidirectional"))
    )
    (net (code "46") (name "MCBMB10(0)") (class "Default")
      (node (ref "E15") (pin "6") (pinfunction "A3_6") (pintype "input"))
      (node (ref "H03") (pin "T2") (pinfunction "1_T2") (pintype "bidirectional"))
    )
    (net (code "47") (name "MCBMB11(0)") (class "Default")
      (node (ref "E15") (pin "8") (pinfunction "A4_8") (pintype "input"))
      (node (ref "H03") (pin "V2") (pinfunction "1_V2") (pintype "bidirectional"))
    )
    (net (code "48") (name "MEM00") (class "Default")
      (node (ref "E12") (pin "18") (pinfunction "Y1_18") (pintype "tri_state"))
      (node (ref "H04") (pin "E2") (pinfunction "1_E2") (pintype "bidirectional"))
    )
    (net (code "49") (name "MEM01") (class "Default")
      (node (ref "E12") (pin "16") (pinfunction "Y2_16") (pintype "tri_state"))
      (node (ref "H04") (pin "H2") (pinfunction "1_H2") (pintype "bidirectional"))
    )
    (net (code "50") (name "MEM02") (class "Default")
      (node (ref "E12") (pin "14") (pinfunction "Y3_14") (pintype "tri_state"))
      (node (ref "H04") (pin "K2") (pinfunction "1_K2") (pintype "bidirectional"))
    )
    (net (code "51") (name "MEM03") (class "Default")
      (node (ref "E12") (pin "12") (pinfunction "Y4_12") (pintype "tri_state"))
      (node (ref "H04") (pin "M2") (pinfunction "1_M2") (pintype "bidirectional"))
    )
    (net (code "52") (name "MEM04") (class "Default")
      (node (ref "E12") (pin "9") (pinfunction "Y1_9") (pintype "tri_state"))
      (node (ref "H04") (pin "P2") (pinfunction "1_P2") (pintype "bidirectional"))
    )
    (net (code "53") (name "MEM05") (class "Default")
      (node (ref "E12") (pin "7") (pinfunction "Y2_7") (pintype "tri_state"))
      (node (ref "H04") (pin "S2") (pinfunction "1_S2") (pintype "bidirectional"))
    )
    (net (code "54") (name "MEM06") (class "Default")
      (node (ref "E12") (pin "5") (pinfunction "Y3_5") (pintype "tri_state"))
      (node (ref "H04") (pin "T2") (pinfunction "1_T2") (pintype "bidirectional"))
    )
    (net (code "55") (name "MEM07") (class "Default")
      (node (ref "E12") (pin "3") (pinfunction "Y4_3") (pintype "tri_state"))
      (node (ref "H04") (pin "V2") (pinfunction "1_V2") (pintype "bidirectional"))
    )
    (net (code "56") (name "MEM08") (class "Default")
      (node (ref "E13") (pin "18") (pinfunction "Y1_18") (pintype "tri_state"))
      (node (ref "H05") (pin "D2") (pinfunction "1_D2") (pintype "bidirectional"))
      (node (ref "SV4") (pin "41") (pinfunction "41_41") (pintype "passive"))
      (node (ref "SV5") (pin "41") (pinfunction "41_41") (pintype "passive"))
    )
    (net (code "57") (name "MEM09") (class "Default")
      (node (ref "E13") (pin "16") (pinfunction "Y2_16") (pintype "tri_state"))
      (node (ref "H05") (pin "E2") (pinfunction "1_E2") (pintype "bidirectional"))
      (node (ref "SV4") (pin "39") (pinfunction "39_39") (pintype "passive"))
      (node (ref "SV5") (pin "39") (pinfunction "39_39") (pintype "passive"))
    )
    (net (code "58") (name "MEM10") (class "Default")
      (node (ref "E13") (pin "14") (pinfunction "Y3_14") (pintype "tri_state"))
      (node (ref "H05") (pin "H2") (pinfunction "1_H2") (pintype "bidirectional"))
      (node (ref "SV4") (pin "40") (pinfunction "40_40") (pintype "passive"))
      (node (ref "SV5") (pin "40") (pinfunction "40_40") (pintype "passive"))
    )
    (net (code "59") (name "MEM11") (class "Default")
      (node (ref "E13") (pin "12") (pinfunction "Y4_12") (pintype "tri_state"))
      (node (ref "H05") (pin "K2") (pinfunction "1_K2") (pintype "bidirectional"))
      (node (ref "SV4") (pin "37") (pinfunction "37_37") (pintype "passive"))
      (node (ref "SV5") (pin "37") (pinfunction "37_37") (pintype "passive"))
    )
    (net (code "60") (name "MEMDONE(0)") (class "Default")
      (node (ref "E5") (pin "1") (pinfunction "O_1") (pintype "open_collector"))
      (node (ref "H05") (pin "S2") (pinfunction "1_S2") (pintype "bidirectional"))
    )
    (net (code "61") (name "MEMDONE(1)") (class "Default")
      (node (ref "E5") (pin "2") (pinfunction "I0_2") (pintype "input"))
      (node (ref "E5") (pin "3") (pinfunction "I1_3") (pintype "input"))
      (node (ref "E9") (pin "5") (pinfunction "Q_5") (pintype "output"))
      (node (ref "IC2") (pin "5") (pinfunction "Q_5") (pintype "output"))
    )
    (net (code "62") (name "MEMSTART(0)") (class "Default")
      (node (ref "E1") (pin "6") (pinfunction "O_6") (pintype "output"))
      (node (ref "E4") (pin "1") (pinfunction "IN_1") (pintype "input"))
      (node (ref "IC1") (pin "1") (pinfunction "A_1") (pintype "input"))
      (node (ref "IC1") (pin "9") (pinfunction "A_9") (pintype "input"))
      (node (ref "RESET") (pin "3") (pinfunction "3_3") (pintype "passive"))
    )
    (net (code "63") (name "MEMSTART(1)") (class "Default")
      (node (ref "E1") (pin "5") (pinfunction "I1_5") (pintype "input"))
      (node (ref "H05") (pin "M2") (pinfunction "1_M2") (pintype "bidirectional"))
      (node (ref "R1") (pin "1") (pinfunction "1_1") (pintype "passive"))
    )
    (net (code "64") (name "MEM_P") (class "Default")
      (node (ref "E13") (pin "9") (pinfunction "Y1_9") (pintype "tri_state"))
      (node (ref "H04") (pin "D2") (pinfunction "1_D2") (pintype "bidirectional"))
    )
    (net (code "65") (name "MS100") (class "Default")
      (node (ref "E1") (pin "12") (pinfunction "I0_12") (pintype "input"))
      (node (ref "E1") (pin "13") (pinfunction "I1_13") (pintype "input"))
      (node (ref "E4") (pin "2") (pinfunction "TAP2_2") (pintype "output"))
    )
    (net (code "66") (name "MS150") (class "Default")
      (node (ref "E11") (pin "4") (pinfunction "PRE_4") (pintype "input"))
      (node (ref "E4") (pin "6") (pinfunction "TAP3_6") (pintype "output"))
    )
    (net (code "67") (name "MS250") (class "Default")
      (node (ref "E3") (pin "1") (pinfunction "IN_1") (pintype "input"))
      (node (ref "E4") (pin "5") (pinfunction "TAP5_5") (pintype "output"))
    )
    (net (code "68") (name "MS350") (class "Default")
      (node (ref "E10") (pin "4") (pinfunction "PRE_4") (pintype "input"))
      (node (ref "E3") (pin "2") (pinfunction "TAP2_2") (pintype "output"))
    )
    (net (code "69") (name "MS400") (class "Default")
      (node (ref "E10") (pin "1") (pinfunction "CLR_1") (pintype "input"))
      (node (ref "E3") (pin "6") (pinfunction "TAP3_6") (pintype "output"))
    )
    (net (code "70") (name "MS500") (class "Default")
      (node (ref "E2") (pin "1") (pinfunction "IN_1") (pintype "input"))
      (node (ref "E3") (pin "5") (pinfunction "TAP5_5") (pintype "output"))
    )
    (net (code "71") (name "MS650") (class "Default")
      (node (ref "E11") (pin "1") (pinfunction "CLR_1") (pintype "input"))
      (node (ref "E2") (pin "6") (pinfunction "TAP3_6") (pintype "output"))
    )
    (net (code "72") (name "NS100") (class "Default")
      (node (ref "E1") (pin "11") (pinfunction "O_11") (pintype "output"))
      (node (ref "E11") (pin "11") (pinfunction "CLK_11") (pintype "input"))
    )
    (net (code "73") (name "Net-(E1C-I0)") (class "Default")
      (node (ref "E1") (pin "10") (pinfunction "I1_10") (pintype "input"))
      (node (ref "E1") (pin "9") (pinfunction "I0_9") (pintype "input"))
      (node (ref "RESET") (pin "2") (pinfunction "2_2") (pintype "passive"))
    )
    (net (code "74") (name "Net-(E16-I{slash}O5)") (class "Default")
      (node (ref "E16") (pin "17") (pinfunction "I/O5_17") (pintype "bidirectional"))
      (node (ref "E16A") (pin "17") (pinfunction "I/O5_17") (pintype "bidirectional"))
    )
    (net (code "75") (name "Net-(E16-I{slash}O6)") (class "Default")
      (node (ref "E16") (pin "18") (pinfunction "I/O6_18") (pintype "bidirectional"))
      (node (ref "E16A") (pin "18") (pinfunction "I/O6_18") (pintype "bidirectional"))
    )
    (net (code "76") (name "Net-(E16-I{slash}O7)") (class "Default")
      (node (ref "E16") (pin "19") (pinfunction "I/O7_19") (pintype "bidirectional"))
      (node (ref "E16A") (pin "19") (pinfunction "I/O7_19") (pintype "bidirectional"))
    )
    (net (code "77") (name "Net-(E18A-I0)") (class "Default")
      (node (ref "E18") (pin "1") (pinfunction "I0_1") (pintype "input"))
      (node (ref "FIELDS") (pin "2") (pinfunction "2_2") (pintype "passive"))
    )
    (net (code "78") (name "Net-(E18A-I1)") (class "Default")
      (node (ref "E18") (pin "2") (pinfunction "I1_2") (pintype "input"))
      (node (ref "FIELDS") (pin "4") (pinfunction "4_4") (pintype "passive"))
    )
    (net (code "79") (name "Net-(E18A-I2)") (class "Default")
      (node (ref "E18") (pin "3") (pinfunction "I2_3") (pintype "input"))
      (node (ref "FIELDS") (pin "6") (pinfunction "6_6") (pintype "passive"))
    )
    (net (code "80") (name "Net-(E18A-I3)") (class "Default")
      (node (ref "E18") (pin "4") (pinfunction "I3_4") (pintype "input"))
      (node (ref "FIELDS") (pin "8") (pinfunction "8_8") (pintype "passive"))
    )
    (net (code "81") (name "Net-(E18A-I4)") (class "Default")
      (node (ref "E18") (pin "5") (pinfunction "I4_5") (pintype "input"))
      (node (ref "FIELDS") (pin "10") (pinfunction "10_10") (pintype "passive"))
    )
    (net (code "82") (name "Net-(E18A-I5)") (class "Default")
      (node (ref "E18") (pin "6") (pinfunction "I5_6") (pintype "input"))
      (node (ref "FIELDS") (pin "12") (pinfunction "12_12") (pintype "passive"))
    )
    (net (code "83") (name "Net-(E18A-I6)") (class "Default")
      (node (ref "E18") (pin "11") (pinfunction "I6_11") (pintype "input"))
      (node (ref "FIELDS") (pin "16") (pinfunction "16_16") (pintype "passive"))
    )
    (net (code "84") (name "Net-(E18A-I7)") (class "Default")
      (node (ref "E18") (pin "12") (pinfunction "I7_12") (pintype "input"))
      (node (ref "FIELDS") (pin "14") (pinfunction "14_14") (pintype "passive"))
    )
    (net (code "85") (name "Net-(E19A-Y0)") (class "Default")
      (node (ref "E19") (pin "15") (pinfunction "Y0_15") (pintype "output"))
      (node (ref "FIELDS") (pin "1") (pinfunction "1_1") (pintype "passive"))
    )
    (net (code "86") (name "Net-(E19A-Y1)") (class "Default")
      (node (ref "E19") (pin "14") (pinfunction "Y1_14") (pintype "output"))
      (node (ref "FIELDS") (pin "3") (pinfunction "3_3") (pintype "passive"))
    )
    (net (code "87") (name "Net-(E19A-Y2)") (class "Default")
      (node (ref "E19") (pin "13") (pinfunction "Y2_13") (pintype "output"))
      (node (ref "FIELDS") (pin "5") (pinfunction "5_5") (pintype "passive"))
    )
    (net (code "88") (name "Net-(E19A-Y3)") (class "Default")
      (node (ref "E19") (pin "12") (pinfunction "Y3_12") (pintype "output"))
      (node (ref "FIELDS") (pin "7") (pinfunction "7_7") (pintype "passive"))
    )
    (net (code "89") (name "Net-(E19A-Y4)") (class "Default")
      (node (ref "E19") (pin "11") (pinfunction "Y4_11") (pintype "output"))
      (node (ref "FIELDS") (pin "9") (pinfunction "9_9") (pintype "passive"))
    )
    (net (code "90") (name "Net-(E19A-Y5)") (class "Default")
      (node (ref "E19") (pin "10") (pinfunction "Y5_10") (pintype "output"))
      (node (ref "FIELDS") (pin "11") (pinfunction "11_11") (pintype "passive"))
    )
    (net (code "91") (name "Net-(E19A-Y6)") (class "Default")
      (node (ref "E19") (pin "9") (pinfunction "Y6_9") (pintype "output"))
      (node (ref "FIELDS") (pin "13") (pinfunction "13_13") (pintype "passive"))
    )
    (net (code "92") (name "Net-(E19A-Y7)") (class "Default")
      (node (ref "E19") (pin "7") (pinfunction "Y7_7") (pintype "output"))
      (node (ref "FIELDS") (pin "15") (pinfunction "15_15") (pintype "passive"))
    )
    (net (code "93") (name "OE(0)") (class "Default")
      (node (ref "E11") (pin "6") (pinfunction "~{Q}_6") (pintype "output"))
      (node (ref "E12") (pin "1") (pinfunction "G_1") (pintype "input"))
      (node (ref "E12") (pin "19") (pinfunction "G_19") (pintype "input"))
      (node (ref "E13") (pin "1") (pinfunction "G_1") (pintype "input"))
      (node (ref "E13") (pin "19") (pinfunction "G_19") (pintype "input"))
      (node (ref "E16") (pin "22") (pinfunction "~{OE}_22") (pintype "input"))
      (node (ref "E16A") (pin "22") (pinfunction "~{OE}_22") (pintype "input"))
      (node (ref "E17") (pin "22") (pinfunction "~{OE}_22") (pintype "input"))
      (node (ref "E17A") (pin "22") (pinfunction "~{OE}_22") (pintype "input"))
      (node (ref "E20") (pin "12") (pinfunction "I0_12") (pintype "input"))
      (node (ref "IC1") (pin "4") (pinfunction "~{Q}_4") (pintype "output"))
      (node (ref "SV2") (pin "22") (pinfunction "22_22") (pintype "passive"))
      (node (ref "SV4") (pin "22") (pinfunction "22_22") (pintype "passive"))
      (node (ref "SV5") (pin "22") (pinfunction "22_22") (pintype "passive"))
    )
    (net (code "94") (name "PARITY") (class "Default")
      (node (ref "E13") (pin "11") (pinfunction "A1_11") (pintype "input"))
      (node (ref "E13") (pin "13") (pinfunction "A2_13") (pintype "input"))
      (node (ref "E13") (pin "15") (pinfunction "A3_15") (pintype "input"))
      (node (ref "E13") (pin "17") (pinfunction "A4_17") (pintype "input"))
      (node (ref "E15") (pin "9") (pinfunction "Y1_9") (pintype "tri_state"))
      (node (ref "E16") (pin "16") (pinfunction "I/O4_16") (pintype "bidirectional"))
      (node (ref "E16A") (pin "16") (pinfunction "I/O4_16") (pintype "bidirectional"))
      (node (ref "SV2") (pin "3") (pinfunction "3_3") (pintype "passive"))
      (node (ref "SV3") (pin "3") (pinfunction "3_3") (pintype "passive"))
      (node (ref "SV4") (pin "3") (pinfunction "3_3") (pintype "passive"))
    )
    (net (code "95") (name "PWR_OK(1)") (class "Default")
      (node (ref "C1") (pin "1") (pinfunction "1_1") (pintype "passive"))
      (node (ref "D1") (pin "A") (pinfunction "A_A") (pintype "passive"))
      (node (ref "R3") (pin "1") (pinfunction "1_1") (pintype "passive"))
      (node (ref "RESET") (pin "1") (pinfunction "1_1") (pintype "passive"))
    )
    (net (code "96") (name "RESET") (class "Default")
      (node (ref "E1") (pin "8") (pinfunction "O_8") (pintype "output"))
      (node (ref "E10") (pin "11") (pinfunction "CLK_11") (pintype "input"))
      (node (ref "E10") (pin "3") (pinfunction "CLK_3") (pintype "input"))
      (node (ref "E11") (pin "3") (pinfunction "CLK_3") (pintype "input"))
      (node (ref "E9") (pin "3") (pinfunction "CLK_3") (pintype "input"))
    )
    (net (code "97") (name "SDELAY") (class "Default")
      (node (ref "IC1") (pin "5") (pinfunction "Q_5") (pintype "output"))
      (node (ref "IC2") (pin "1") (pinfunction "A_1") (pintype "input"))
    )
    (net (code "98") (name "STROBE(0)") (class "Default")
      (node (ref "E5") (pin "4") (pinfunction "O_4") (pintype "open_collector"))
      (node (ref "H05") (pin "P2") (pinfunction "1_P2") (pintype "bidirectional"))
    )
    (net (code "99") (name "STROBE(1)") (class "Default")
      (node (ref "E10") (pin "5") (pinfunction "Q_5") (pintype "output"))
      (node (ref "E5") (pin "5") (pinfunction "I0_5") (pintype "input"))
      (node (ref "E5") (pin "6") (pinfunction "I1_6") (pintype "input"))
      (node (ref "IC2") (pin "13") (pinfunction "Q_13") (pintype "output"))
    )
    (net (code "100") (name "TP150") (class "Default")
      (node (ref "E10") (pin "10") (pinfunction "PRE_10") (pintype "input"))
      (node (ref "E8") (pin "6") (pinfunction "TAP3_6") (pintype "output"))
    )
    (net (code "101") (name "TP250") (class "Default")
      (node (ref "E7") (pin "1") (pinfunction "IN_1") (pintype "input"))
      (node (ref "E8") (pin "5") (pinfunction "TAP5_5") (pintype "output"))
    )
    (net (code "102") (name "TP300") (class "Default")
      (node (ref "E10") (pin "13") (pinfunction "CLR_13") (pintype "input"))
      (node (ref "E7") (pin "7") (pinfunction "TAP1_7") (pintype "output"))
    )
    (net (code "103") (name "TP500") (class "Default")
      (node (ref "E11") (pin "13") (pinfunction "CLR_13") (pintype "input"))
      (node (ref "E6") (pin "1") (pinfunction "IN_1") (pintype "input"))
      (node (ref "E7") (pin "5") (pinfunction "TAP5_5") (pintype "output"))
      (node (ref "E9") (pin "4") (pinfunction "PRE_4") (pintype "input"))
    )
    (net (code "104") (name "TP550") (class "Default")
      (node (ref "E6") (pin "7") (pinfunction "TAP1_7") (pintype "output"))
      (node (ref "E9") (pin "1") (pinfunction "CLR_1") (pintype "input"))
    )
    (net (code "105") (name "VCC") (class "Default")
      (node (ref "C10") (pin "1") (pinfunction "1_1") (pintype "passive"))
      (node (ref "C11") (pin "1") (pinfunction "1_1") (pintype "passive"))
      (node (ref "C12") (pin "1") (pinfunction "1_1") (pintype "passive"))
      (node (ref "C13") (pin "1") (pinfunction "1_1") (pintype "passive"))
      (node (ref "C14") (pin "1") (pinfunction "1_1") (pintype "passive"))
      (node (ref "C15") (pin "1") (pinfunction "1_1") (pintype "passive"))
      (node (ref "C16") (pin "1") (pinfunction "1_1") (pintype "passive"))
      (node (ref "C2") (pin "1") (pinfunction "1_1") (pintype "passive"))
      (node (ref "C3") (pin "1") (pinfunction "1_1") (pintype "passive"))
      (node (ref "C4") (pin "1") (pinfunction "1_1") (pintype "passive"))
      (node (ref "C5") (pin "1") (pinfunction "1_1") (pintype "passive"))
      (node (ref "C6") (pin "1") (pinfunction "1_1") (pintype "passive"))
      (node (ref "C7") (pin "1") (pinfunction "1_1") (pintype "passive"))
      (node (ref "C8") (pin "1") (pinfunction "1_1") (pintype "passive"))
      (node (ref "C9") (pin "1") (pinfunction "1_1") (pintype "passive"))
      (node (ref "D1") (pin "C") (pinfunction "C_C") (pintype "passive"))
      (node (ref "E11") (pin "10") (pinfunction "PRE_10") (pintype "input"))
      (node (ref "E16") (pin "28") (pinfunction "VCC_28") (pintype "power_in"))
      (node (ref "E16A") (pin "28") (pinfunction "VCC_28") (pintype "power_in"))
      (node (ref "E17") (pin "28") (pinfunction "VCC_28") (pintype "power_in"))
      (node (ref "E17A") (pin "28") (pinfunction "VCC_28") (pintype "power_in"))
      (node (ref "E19") (pin "6") (pinfunction "G1_6") (pintype "input"))
      (node (ref "E5") (pin "11") (pinfunction "I0_11") (pintype "input"))
      (node (ref "E5") (pin "12") (pinfunction "I1_12") (pintype "input"))
      (node (ref "E5") (pin "8") (pinfunction "I0_8") (pintype "input"))
      (node (ref "E5") (pin "9") (pinfunction "I1_9") (pintype "input"))
      (node (ref "E9") (pin "10") (pinfunction "PRE_10") (pintype "input"))
      (node (ref "E9") (pin "11") (pinfunction "CLK_11") (pintype "input"))
      (node (ref "E9") (pin "12") (pinfunction "D_12") (pintype "input"))
      (node (ref "E9") (pin "13") (pinfunction "CLR_13") (pintype "input"))
      (node (ref "R3") (pin "2") (pinfunction "2_2") (pintype "passive"))
      (node (ref "SV1") (pin "49") (pinfunction "49_49") (pintype "passive"))
      (node (ref "SV1") (pin "50") (pinfunction "50_50") (pintype "passive"))
      (node (ref "SV2") (pin "49") (pinfunction "49_49") (pintype "passive"))
      (node (ref "SV2") (pin "50") (pinfunction "50_50") (pintype "passive"))
      (node (ref "SV3") (pin "49") (pinfunction "49_49") (pintype "passive"))
      (node (ref "SV3") (pin "50") (pinfunction "50_50") (pintype "passive"))
      (node (ref "SV4") (pin "49") (pinfunction "49_49") (pintype "passive"))
      (node (ref "SV4") (pin "50") (pinfunction "50_50") (pintype "passive"))
      (node (ref "SV5") (pin "49") (pinfunction "49_49") (pintype "passive"))
      (node (ref "SV5") (pin "50") (pinfunction "50_50") (pintype "passive"))
      (node (ref "X1") (pin "1") (pinfunction "KL_1") (pintype "passive"))
    )
    (net (code "106") (name "WE(0)") (class "Default")
      (node (ref "E10") (pin "8") (pinfunction "~{Q}_8") (pintype "output"))
      (node (ref "E14") (pin "1") (pinfunction "G_1") (pintype "input"))
      (node (ref "E14") (pin "19") (pinfunction "G_19") (pintype "input"))
      (node (ref "E15") (pin "1") (pinfunction "G_1") (pintype "input"))
      (node (ref "E15") (pin "19") (pinfunction "G_19") (pintype "input"))
      (node (ref "E16") (pin "27") (pinfunction "~{WE}_27") (pintype "input"))
      (node (ref "E16A") (pin "27") (pinfunction "~{WE}_27") (pintype "input"))
      (node (ref "E17") (pin "27") (pinfunction "~{WE}_27") (pintype "input"))
      (node (ref "E17A") (pin "27") (pinfunction "~{WE}_27") (pintype "input"))
      (node (ref "E20") (pin "13") (pinfunction "I1_13") (pintype "input"))
      (node (ref "IC3") (pin "4") (pinfunction "~{Q}_4") (pintype "output"))
      (node (ref "SV2") (pin "32") (pinfunction "32_32") (pintype "passive"))
      (node (ref "SV3") (pin "32") (pinfunction "32_32") (pintype "passive"))
      (node (ref "SV5") (pin "32") (pinfunction "32_32") (pintype "passive"))
    )
    (net (code "107") (name "unconnected-(E2A-TAP1-Pad7)") (class "Default")
      (node (ref "E2") (pin "7") (pinfunction "TAP1_7") (pintype "output"))
    )
    (net (code "108") (name "unconnected-(E2A-TAP2-Pad2)") (class "Default")
      (node (ref "E2") (pin "2") (pinfunction "TAP2_2") (pintype "output"))
    )
    (net (code "109") (name "unconnected-(E2A-TAP4-Pad3)") (class "Default")
      (node (ref "E2") (pin "3") (pinfunction "TAP4_3") (pintype "output"))
    )
    (net (code "110") (name "unconnected-(E2A-TAP5-Pad5)") (class "Default")
      (node (ref "E2") (pin "5") (pinfunction "TAP5_5") (pintype "output"))
    )
    (net (code "111") (name "unconnected-(E3A-TAP1-Pad7)") (class "Default")
      (node (ref "E3") (pin "7") (pinfunction "TAP1_7") (pintype "output"))
    )
    (net (code "112") (name "unconnected-(E3A-TAP4-Pad3)") (class "Default")
      (node (ref "E3") (pin "3") (pinfunction "TAP4_3") (pintype "output"))
    )
    (net (code "113") (name "unconnected-(E4A-TAP1-Pad7)") (class "Default")
      (node (ref "E4") (pin "7") (pinfunction "TAP1_7") (pintype "output"))
    )
    (net (code "114") (name "unconnected-(E4A-TAP4-Pad3)") (class "Default")
      (node (ref "E4") (pin "3") (pinfunction "TAP4_3") (pintype "output"))
    )
    (net (code "115") (name "unconnected-(E5C-O-Pad10)") (class "Default")
      (node (ref "E5") (pin "10") (pinfunction "O_10") (pintype "open_collector"))
    )
    (net (code "116") (name "unconnected-(E5D-O-Pad13)") (class "Default")
      (node (ref "E5") (pin "13") (pinfunction "O_13") (pintype "open_collector"))
    )
    (net (code "117") (name "unconnected-(E6A-TAP2-Pad2)") (class "Default")
      (node (ref "E6") (pin "2") (pinfunction "TAP2_2") (pintype "output"))
    )
    (net (code "118") (name "unconnected-(E6A-TAP3-Pad6)") (class "Default")
      (node (ref "E6") (pin "6") (pinfunction "TAP3_6") (pintype "output"))
    )
    (net (code "119") (name "unconnected-(E6A-TAP4-Pad3)") (class "Default")
      (node (ref "E6") (pin "3") (pinfunction "TAP4_3") (pintype "output"))
    )
    (net (code "120") (name "unconnected-(E6A-TAP5-Pad5)") (class "Default")
      (node (ref "E6") (pin "5") (pinfunction "TAP5_5") (pintype "output"))
    )
    (net (code "121") (name "unconnected-(E7A-TAP2-Pad2)") (class "Default")
      (node (ref "E7") (pin "2") (pinfunction "TAP2_2") (pintype "output"))
    )
    (net (code "122") (name "unconnected-(E7A-TAP3-Pad6)") (class "Default")
      (node (ref "E7") (pin "6") (pinfunction "TAP3_6") (pintype "output"))
    )
    (net (code "123") (name "unconnected-(E7A-TAP4-Pad3)") (class "Default")
      (node (ref "E7") (pin "3") (pinfunction "TAP4_3") (pintype "output"))
    )
    (net (code "124") (name "unconnected-(E8A-TAP1-Pad7)") (class "Default")
      (node (ref "E8") (pin "7") (pinfunction "TAP1_7") (pintype "output"))
    )
    (net (code "125") (name "unconnected-(E8A-TAP2-Pad2)") (class "Default")
      (node (ref "E8") (pin "2") (pinfunction "TAP2_2") (pintype "output"))
    )
    (net (code "126") (name "unconnected-(E8A-TAP4-Pad3)") (class "Default")
      (node (ref "E8") (pin "3") (pinfunction "TAP4_3") (pintype "output"))
    )
    (net (code "127") (name "unconnected-(E9A-~{Q}-Pad6)") (class "Default")
      (node (ref "E9") (pin "6") (pinfunction "~{Q}_6") (pintype "output"))
    )
    (net (code "128") (name "unconnected-(E9B-Q-Pad9)") (class "Default")
      (node (ref "E9") (pin "9") (pinfunction "Q_9") (pintype "output"))
    )
    (net (code "129") (name "unconnected-(E9B-~{Q}-Pad8)") (class "Default")
      (node (ref "E9") (pin "8") (pinfunction "~{Q}_8") (pintype "output"))
    )
    (net (code "130") (name "unconnected-(E10A-~{Q}-Pad6)") (class "Default")
      (node (ref "E10") (pin "6") (pinfunction "~{Q}_6") (pintype "output"))
    )
    (net (code "131") (name "unconnected-(E10B-Q-Pad9)") (class "Default")
      (node (ref "E10") (pin "9") (pinfunction "Q_9") (pintype "output"))
    )
    (net (code "132") (name "unconnected-(E11A-Q-Pad5)") (class "Default")
      (node (ref "E11") (pin "5") (pinfunction "Q_5") (pintype "output"))
    )
    (net (code "133") (name "unconnected-(E11B-Q-Pad9)") (class "Default")
      (node (ref "E11") (pin "9") (pinfunction "Q_9") (pintype "output"))
    )
    (net (code "134") (name "unconnected-(E13B-Y2-Pad7)") (class "Default")
      (node (ref "E13") (pin "7") (pinfunction "Y2_7") (pintype "tri_state"))
    )
    (net (code "135") (name "unconnected-(E13B-Y3-Pad5)") (class "Default")
      (node (ref "E13") (pin "5") (pinfunction "Y3_5") (pintype "tri_state"))
    )
    (net (code "136") (name "unconnected-(E13B-Y4-Pad3)") (class "Default")
      (node (ref "E13") (pin "3") (pinfunction "Y4_3") (pintype "tri_state"))
    )
    (net (code "137") (name "unconnected-(E15B-Y2-Pad7)") (class "Default")
      (node (ref "E15") (pin "7") (pinfunction "Y2_7") (pintype "tri_state"))
    )
    (net (code "138") (name "unconnected-(E15B-Y3-Pad5)") (class "Default")
      (node (ref "E15") (pin "5") (pinfunction "Y3_5") (pintype "tri_state"))
    )
    (net (code "139") (name "unconnected-(E15B-Y4-Pad3)") (class "Default")
      (node (ref "E15") (pin "3") (pinfunction "Y4_3") (pintype "tri_state"))
    )
    (net (code "140") (name "unconnected-(IC1A-B-Pad2)") (class "Default")
      (node (ref "IC1") (pin "2") (pinfunction "B_2") (pintype "input"))
    )
    (net (code "141") (name "unconnected-(IC1A-C-Pad14)") (class "Default")
      (node (ref "IC1") (pin "14") (pinfunction "C_14") (pintype "input"))
    )
    (net (code "142") (name "unconnected-(IC1A-CLR-Pad3)") (class "Default")
      (node (ref "IC1") (pin "3") (pinfunction "CLR_3") (pintype "input"))
    )
    (net (code "143") (name "unconnected-(IC1A-Q-Pad13)") (class "Default")
      (node (ref "IC1") (pin "13") (pinfunction "Q_13") (pintype "output"))
    )
    (net (code "144") (name "unconnected-(IC1A-R{slash}C-Pad15)") (class "Default")
      (node (ref "IC1") (pin "15") (pinfunction "R/C_15") (pintype "input"))
    )
    (net (code "145") (name "unconnected-(IC1B-B-Pad10)") (class "Default")
      (node (ref "IC1") (pin "10") (pinfunction "B_10") (pintype "input"))
    )
    (net (code "146") (name "unconnected-(IC1B-C-Pad6)") (class "Default")
      (node (ref "IC1") (pin "6") (pinfunction "C_6") (pintype "input"))
    )
    (net (code "147") (name "unconnected-(IC1B-CLR-Pad11)") (class "Default")
      (node (ref "IC1") (pin "11") (pinfunction "CLR_11") (pintype "input"))
    )
    (net (code "148") (name "unconnected-(IC1B-R{slash}C-Pad7)") (class "Default")
      (node (ref "IC1") (pin "7") (pinfunction "R/C_7") (pintype "input"))
    )
    (net (code "149") (name "unconnected-(IC1B-~{Q}-Pad12)") (class "Default")
      (node (ref "IC1") (pin "12") (pinfunction "~{Q}_12") (pintype "output"))
    )
    (net (code "150") (name "unconnected-(IC2A-B-Pad2)") (class "Default")
      (node (ref "IC2") (pin "2") (pinfunction "B_2") (pintype "input"))
    )
    (net (code "151") (name "unconnected-(IC2A-C-Pad14)") (class "Default")
      (node (ref "IC2") (pin "14") (pinfunction "C_14") (pintype "input"))
    )
    (net (code "152") (name "unconnected-(IC2A-CLR-Pad3)") (class "Default")
      (node (ref "IC2") (pin "3") (pinfunction "CLR_3") (pintype "input"))
    )
    (net (code "153") (name "unconnected-(IC2A-R{slash}C-Pad15)") (class "Default")
      (node (ref "IC2") (pin "15") (pinfunction "R/C_15") (pintype "input"))
    )
    (net (code "154") (name "unconnected-(IC2A-~{Q}-Pad4)") (class "Default")
      (node (ref "IC2") (pin "4") (pinfunction "~{Q}_4") (pintype "output"))
    )
    (net (code "155") (name "unconnected-(IC2B-B-Pad10)") (class "Default")
      (node (ref "IC2") (pin "10") (pinfunction "B_10") (pintype "input"))
    )
    (net (code "156") (name "unconnected-(IC2B-C-Pad6)") (class "Default")
      (node (ref "IC2") (pin "6") (pinfunction "C_6") (pintype "input"))
    )
    (net (code "157") (name "unconnected-(IC2B-CLR-Pad11)") (class "Default")
      (node (ref "IC2") (pin "11") (pinfunction "CLR_11") (pintype "input"))
    )
    (net (code "158") (name "unconnected-(IC2B-R{slash}C-Pad7)") (class "Default")
      (node (ref "IC2") (pin "7") (pinfunction "R/C_7") (pintype "input"))
    )
    (net (code "159") (name "unconnected-(IC2B-~{Q}-Pad12)") (class "Default")
      (node (ref "IC2") (pin "12") (pinfunction "~{Q}_12") (pintype "output"))
    )
    (net (code "160") (name "unconnected-(IC3A-B-Pad2)") (class "Default")
      (node (ref "IC3") (pin "2") (pinfunction "B_2") (pintype "input"))
    )
    (net (code "161") (name "unconnected-(IC3A-C-Pad14)") (class "Default")
      (node (ref "IC3") (pin "14") (pinfunction "C_14") (pintype "input"))
    )
    (net (code "162") (name "unconnected-(IC3A-CLR-Pad3)") (class "Default")
      (node (ref "IC3") (pin "3") (pinfunction "CLR_3") (pintype "input"))
    )
    (net (code "163") (name "unconnected-(IC3A-Q-Pad13)") (class "Default")
      (node (ref "IC3") (pin "13") (pinfunction "Q_13") (pintype "output"))
    )
    (net (code "164") (name "unconnected-(IC3A-R{slash}C-Pad15)") (class "Default")
      (node (ref "IC3") (pin "15") (pinfunction "R/C_15") (pintype "input"))
    )
    (net (code "165") (name "unconnected-(IC3B-B-Pad10)") (class "Default")
      (node (ref "IC3") (pin "10") (pinfunction "B_10") (pintype "input"))
    )
    (net (code "166") (name "unconnected-(IC3B-C-Pad6)") (class "Default")
      (node (ref "IC3") (pin "6") (pinfunction "C_6") (pintype "input"))
    )
    (net (code "167") (name "unconnected-(IC3B-CLR-Pad11)") (class "Default")
      (node (ref "IC3") (pin "11") (pinfunction "CLR_11") (pintype "input"))
    )
    (net (code "168") (name "unconnected-(IC3B-R{slash}C-Pad7)") (class "Default")
      (node (ref "IC3") (pin "7") (pinfunction "R/C_7") (pintype "input"))
    )
    (net (code "169") (name "unconnected-(IC3B-~{Q}-Pad12)") (class "Default")
      (node (ref "IC3") (pin "12") (pinfunction "~{Q}_12") (pintype "output"))
    )
    (net (code "170") (name "unconnected-(SV1-Pad3)") (class "Default")
      (node (ref "SV1") (pin "3") (pinfunction "3_3") (pintype "passive"))
    )
    (net (code "171") (name "unconnected-(SV1-Pad4)") (class "Default")
      (node (ref "SV1") (pin "4") (pinfunction "4_4") (pintype "passive"))
    )
    (net (code "172") (name "unconnected-(SV1-Pad5)") (class "Default")
      (node (ref "SV1") (pin "5") (pinfunction "5_5") (pintype "passive"))
    )
    (net (code "173") (name "unconnected-(SV1-Pad6)") (class "Default")
      (node (ref "SV1") (pin "6") (pinfunction "6_6") (pintype "passive"))
    )
    (net (code "174") (name "unconnected-(SV1-Pad7)") (class "Default")
      (node (ref "SV1") (pin "7") (pinfunction "7_7") (pintype "passive"))
    )
    (net (code "175") (name "unconnected-(SV1-Pad8)") (class "Default")
      (node (ref "SV1") (pin "8") (pinfunction "8_8") (pintype "passive"))
    )
    (net (code "176") (name "unconnected-(SV1-Pad9)") (class "Default")
      (node (ref "SV1") (pin "9") (pinfunction "9_9") (pintype "passive"))
    )
    (net (code "177") (name "unconnected-(SV1-Pad10)") (class "Default")
      (node (ref "SV1") (pin "10") (pinfunction "10_10") (pintype "passive"))
    )
    (net (code "178") (name "unconnected-(SV1-Pad11)") (class "Default")
      (node (ref "SV1") (pin "11") (pinfunction "11_11") (pintype "passive"))
    )
    (net (code "179") (name "unconnected-(SV1-Pad12)") (class "Default")
      (node (ref "SV1") (pin "12") (pinfunction "12_12") (pintype "passive"))
    )
    (net (code "180") (name "unconnected-(SV1-Pad13)") (class "Default")
      (node (ref "SV1") (pin "13") (pinfunction "13_13") (pintype "passive"))
    )
    (net (code "181") (name "unconnected-(SV1-Pad14)") (class "Default")
      (node (ref "SV1") (pin "14") (pinfunction "14_14") (pintype "passive"))
    )
    (net (code "182") (name "unconnected-(SV1-Pad15)") (class "Default")
      (node (ref "SV1") (pin "15") (pinfunction "15_15") (pintype "passive"))
    )
    (net (code "183") (name "unconnected-(SV1-Pad16)") (class "Default")
      (node (ref "SV1") (pin "16") (pinfunction "16_16") (pintype "passive"))
    )
    (net (code "184") (name "unconnected-(SV1-Pad17)") (class "Default")
      (node (ref "SV1") (pin "17") (pinfunction "17_17") (pintype "passive"))
    )
    (net (code "185") (name "unconnected-(SV1-Pad18)") (class "Default")
      (node (ref "SV1") (pin "18") (pinfunction "18_18") (pintype "passive"))
    )
    (net (code "186") (name "unconnected-(SV1-Pad19)") (class "Default")
      (node (ref "SV1") (pin "19") (pinfunction "19_19") (pintype "passive"))
    )
    (net (code "187") (name "unconnected-(SV1-Pad21)") (class "Default")
      (node (ref "SV1") (pin "21") (pinfunction "21_21") (pintype "passive"))
    )
    (net (code "188") (name "unconnected-(SV1-Pad22)") (class "Default")
      (node (ref "SV1") (pin "22") (pinfunction "22_22") (pintype "passive"))
    )
    (net (code "189") (name "unconnected-(SV1-Pad23)") (class "Default")
      (node (ref "SV1") (pin "23") (pinfunction "23_23") (pintype "passive"))
    )
    (net (code "190") (name "unconnected-(SV1-Pad25)") (class "Default")
      (node (ref "SV1") (pin "25") (pinfunction "25_25") (pintype "passive"))
    )
    (net (code "191") (name "unconnected-(SV1-Pad32)") (class "Default")
      (node (ref "SV1") (pin "32") (pinfunction "32_32") (pintype "passive"))
    )
    (net (code "192") (name "unconnected-(SV1-Pad35)") (class "Default")
      (node (ref "SV1") (pin "35") (pinfunction "35_35") (pintype "passive"))
    )
    (net (code "193") (name "unconnected-(SV1-Pad36)") (class "Default")
      (node (ref "SV1") (pin "36") (pinfunction "36_36") (pintype "passive"))
    )
    (net (code "194") (name "unconnected-(SV1-Pad37)") (class "Default")
      (node (ref "SV1") (pin "37") (pinfunction "37_37") (pintype "passive"))
    )
    (net (code "195") (name "unconnected-(SV1-Pad38)") (class "Default")
      (node (ref "SV1") (pin "38") (pinfunction "38_38") (pintype "passive"))
    )
    (net (code "196") (name "unconnected-(SV1-Pad39)") (class "Default")
      (node (ref "SV1") (pin "39") (pinfunction "39_39") (pintype "passive"))
    )
    (net (code "197") (name "unconnected-(SV1-Pad40)") (class "Default")
      (node (ref "SV1") (pin "40") (pinfunction "40_40") (pintype "passive"))
    )
    (net (code "198") (name "unconnected-(SV1-Pad41)") (class "Default")
      (node (ref "SV1") (pin "41") (pinfunction "41_41") (pintype "passive"))
    )
    (net (code "199") (name "unconnected-(SV1-Pad42)") (class "Default")
      (node (ref "SV1") (pin "42") (pinfunction "42_42") (pintype "passive"))
    )
    (net (code "200") (name "unconnected-(SV1-Pad45)") (class "Default")
      (node (ref "SV1") (pin "45") (pinfunction "45_45") (pintype "passive"))
    )
    (net (code "201") (name "unconnected-(SV1-Pad47)") (class "Default")
      (node (ref "SV1") (pin "47") (pinfunction "47_47") (pintype "passive"))
    )
    (net (code "202") (name "unconnected-(SV1-Pad48)") (class "Default")
      (node (ref "SV1") (pin "48") (pinfunction "48_48") (pintype "passive"))
    )
    (net (code "203") (name "unconnected-(SV2-Pad34)") (class "Default")
      (node (ref "SV2") (pin "34") (pinfunction "34_34") (pintype "passive"))
    )
    (net (code "204") (name "unconnected-(SV2-Pad37)") (class "Default")
      (node (ref "SV2") (pin "37") (pinfunction "37_37") (pintype "passive"))
    )
    (net (code "205") (name "unconnected-(SV2-Pad39)") (class "Default")
      (node (ref "SV2") (pin "39") (pinfunction "39_39") (pintype "passive"))
    )
    (net (code "206") (name "unconnected-(SV2-Pad40)") (class "Default")
      (node (ref "SV2") (pin "40") (pinfunction "40_40") (pintype "passive"))
    )
    (net (code "207") (name "unconnected-(SV2-Pad41)") (class "Default")
      (node (ref "SV2") (pin "41") (pinfunction "41_41") (pintype "passive"))
    )
    (net (code "208") (name "unconnected-(SV2-Pad42)") (class "Default")
      (node (ref "SV2") (pin "42") (pinfunction "42_42") (pintype "passive"))
    )
    (net (code "209") (name "unconnected-(SV2-Pad43)") (class "Default")
      (node (ref "SV2") (pin "43") (pinfunction "43_43") (pintype "passive"))
    )
    (net (code "210") (name "unconnected-(SV2-Pad44)") (class "Default")
      (node (ref "SV2") (pin "44") (pinfunction "44_44") (pintype "passive"))
    )
    (net (code "211") (name "unconnected-(SV2-Pad45)") (class "Default")
      (node (ref "SV2") (pin "45") (pinfunction "45_45") (pintype "passive"))
    )
    (net (code "212") (name "unconnected-(SV2-Pad46)") (class "Default")
      (node (ref "SV2") (pin "46") (pinfunction "46_46") (pintype "passive"))
    )
    (net (code "213") (name "unconnected-(SV2-Pad47)") (class "Default")
      (node (ref "SV2") (pin "47") (pinfunction "47_47") (pintype "passive"))
    )
    (net (code "214") (name "unconnected-(SV2-Pad48)") (class "Default")
      (node (ref "SV2") (pin "48") (pinfunction "48_48") (pintype "passive"))
    )
    (net (code "215") (name "unconnected-(SV3-Pad15)") (class "Default")
      (node (ref "SV3") (pin "15") (pinfunction "15_15") (pintype "passive"))
    )
    (net (code "216") (name "unconnected-(SV3-Pad17)") (class "Default")
      (node (ref "SV3") (pin "17") (pinfunction "17_17") (pintype "passive"))
    )
    (net (code "217") (name "unconnected-(SV3-Pad18)") (class "Default")
      (node (ref "SV3") (pin "18") (pinfunction "18_18") (pintype "passive"))
    )
    (net (code "218") (name "unconnected-(SV3-Pad19)") (class "Default")
      (node (ref "SV3") (pin "19") (pinfunction "19_19") (pintype "passive"))
    )
    (net (code "219") (name "unconnected-(SV3-Pad20)") (class "Default")
      (node (ref "SV3") (pin "20") (pinfunction "20_20") (pintype "passive"))
    )
    (net (code "220") (name "unconnected-(SV3-Pad21)") (class "Default")
      (node (ref "SV3") (pin "21") (pinfunction "21_21") (pintype "passive"))
    )
    (net (code "221") (name "unconnected-(SV3-Pad22)") (class "Default")
      (node (ref "SV3") (pin "22") (pinfunction "22_22") (pintype "passive"))
    )
    (net (code "222") (name "unconnected-(SV3-Pad23)") (class "Default")
      (node (ref "SV3") (pin "23") (pinfunction "23_23") (pintype "passive"))
    )
    (net (code "223") (name "unconnected-(SV3-Pad24)") (class "Default")
      (node (ref "SV3") (pin "24") (pinfunction "24_24") (pintype "passive"))
    )
    (net (code "224") (name "unconnected-(SV3-Pad25)") (class "Default")
      (node (ref "SV3") (pin "25") (pinfunction "25_25") (pintype "passive"))
    )
    (net (code "225") (name "unconnected-(SV3-Pad26)") (class "Default")
      (node (ref "SV3") (pin "26") (pinfunction "26_26") (pintype "passive"))
    )
    (net (code "226") (name "unconnected-(SV3-Pad27)") (class "Default")
      (node (ref "SV3") (pin "27") (pinfunction "27_27") (pintype "passive"))
    )
    (net (code "227") (name "unconnected-(SV3-Pad28)") (class "Default")
      (node (ref "SV3") (pin "28") (pinfunction "28_28") (pintype "passive"))
    )
    (net (code "228") (name "unconnected-(SV3-Pad29)") (class "Default")
      (node (ref "SV3") (pin "29") (pinfunction "29_29") (pintype "passive"))
    )
    (net (code "229") (name "unconnected-(SV3-Pad34)") (class "Default")
      (node (ref "SV3") (pin "34") (pinfunction "34_34") (pintype "passive"))
    )
    (net (code "230") (name "unconnected-(SV3-Pad37)") (class "Default")
      (node (ref "SV3") (pin "37") (pinfunction "37_37") (pintype "passive"))
    )
    (net (code "231") (name "unconnected-(SV3-Pad39)") (class "Default")
      (node (ref "SV3") (pin "39") (pinfunction "39_39") (pintype "passive"))
    )
    (net (code "232") (name "unconnected-(SV3-Pad40)") (class "Default")
      (node (ref "SV3") (pin "40") (pinfunction "40_40") (pintype "passive"))
    )
    (net (code "233") (name "unconnected-(SV3-Pad41)") (class "Default")
      (node (ref "SV3") (pin "41") (pinfunction "41_41") (pintype "passive"))
    )
    (net (code "234") (name "unconnected-(SV3-Pad45)") (class "Default")
      (node (ref "SV3") (pin "45") (pinfunction "45_45") (pintype "passive"))
    )
    (net (code "235") (name "unconnected-(SV3-Pad47)") (class "Default")
      (node (ref "SV3") (pin "47") (pinfunction "47_47") (pintype "passive"))
    )
    (net (code "236") (name "unconnected-(SV3-Pad48)") (class "Default")
      (node (ref "SV3") (pin "48") (pinfunction "48_48") (pintype "passive"))
    )
    (net (code "237") (name "unconnected-(SV4-Pad15)") (class "Default")
      (node (ref "SV4") (pin "15") (pinfunction "15_15") (pintype "passive"))
    )
    (net (code "238") (name "unconnected-(SV4-Pad17)") (class "Default")
      (node (ref "SV4") (pin "17") (pinfunction "17_17") (pintype "passive"))
    )
    (net (code "239") (name "unconnected-(SV4-Pad18)") (class "Default")
      (node (ref "SV4") (pin "18") (pinfunction "18_18") (pintype "passive"))
    )
    (net (code "240") (name "unconnected-(SV4-Pad19)") (class "Default")
      (node (ref "SV4") (pin "19") (pinfunction "19_19") (pintype "passive"))
    )
    (net (code "241") (name "unconnected-(SV4-Pad20)") (class "Default")
      (node (ref "SV4") (pin "20") (pinfunction "20_20") (pintype "passive"))
    )
    (net (code "242") (name "unconnected-(SV4-Pad21)") (class "Default")
      (node (ref "SV4") (pin "21") (pinfunction "21_21") (pintype "passive"))
    )
    (net (code "243") (name "unconnected-(SV4-Pad23)") (class "Default")
      (node (ref "SV4") (pin "23") (pinfunction "23_23") (pintype "passive"))
    )
    (net (code "244") (name "unconnected-(SV4-Pad24)") (class "Default")
      (node (ref "SV4") (pin "24") (pinfunction "24_24") (pintype "passive"))
    )
    (net (code "245") (name "unconnected-(SV4-Pad25)") (class "Default")
      (node (ref "SV4") (pin "25") (pinfunction "25_25") (pintype "passive"))
    )
    (net (code "246") (name "unconnected-(SV4-Pad26)") (class "Default")
      (node (ref "SV4") (pin "26") (pinfunction "26_26") (pintype "passive"))
    )
    (net (code "247") (name "unconnected-(SV4-Pad27)") (class "Default")
      (node (ref "SV4") (pin "27") (pinfunction "27_27") (pintype "passive"))
    )
    (net (code "248") (name "unconnected-(SV4-Pad28)") (class "Default")
      (node (ref "SV4") (pin "28") (pinfunction "28_28") (pintype "passive"))
    )
    (net (code "249") (name "unconnected-(SV4-Pad29)") (class "Default")
      (node (ref "SV4") (pin "29") (pinfunction "29_29") (pintype "passive"))
    )
    (net (code "250") (name "unconnected-(SV4-Pad30)") (class "Default")
      (node (ref "SV4") (pin "30") (pinfunction "30_30") (pintype "passive"))
    )
    (net (code "251") (name "unconnected-(SV4-Pad31)") (class "Default")
      (node (ref "SV4") (pin "31") (pinfunction "31_31") (pintype "passive"))
    )
    (net (code "252") (name "unconnected-(SV4-Pad32)") (class "Default")
      (node (ref "SV4") (pin "32") (pinfunction "32_32") (pintype "passive"))
    )
    (net (code "253") (name "unconnected-(SV4-Pad33)") (class "Default")
      (node (ref "SV4") (pin "33") (pinfunction "33_33") (pintype "passive"))
    )
    (net (code "254") (name "unconnected-(SV4-Pad34)") (class "Default")
      (node (ref "SV4") (pin "34") (pinfunction "34_34") (pintype "passive"))
    )
    (net (code "255") (name "unconnected-(SV4-Pad35)") (class "Default")
      (node (ref "SV4") (pin "35") (pinfunction "35_35") (pintype "passive"))
    )
    (net (code "256") (name "unconnected-(SV4-Pad36)") (class "Default")
      (node (ref "SV4") (pin "36") (pinfunction "36_36") (pintype "passive"))
    )
    (net (code "257") (name "unconnected-(SV4-Pad38)") (class "Default")
      (node (ref "SV4") (pin "38") (pinfunction "38_38") (pintype "passive"))
    )
    (net (code "258") (name "unconnected-(SV4-Pad42)") (class "Default")
      (node (ref "SV4") (pin "42") (pinfunction "42_42") (pintype "passive"))
    )
    (net (code "259") (name "unconnected-(SV4-Pad43)") (class "Default")
      (node (ref "SV4") (pin "43") (pinfunction "43_43") (pintype "passive"))
    )
    (net (code "260") (name "unconnected-(SV4-Pad44)") (class "Default")
      (node (ref "SV4") (pin "44") (pinfunction "44_44") (pintype "passive"))
    )
    (net (code "261") (name "unconnected-(SV4-Pad45)") (class "Default")
      (node (ref "SV4") (pin "45") (pinfunction "45_45") (pintype "passive"))
    )
    (net (code "262") (name "unconnected-(SV4-Pad46)") (class "Default")
      (node (ref "SV4") (pin "46") (pinfunction "46_46") (pintype "passive"))
    )
    (net (code "263") (name "unconnected-(SV4-Pad47)") (class "Default")
      (node (ref "SV4") (pin "47") (pinfunction "47_47") (pintype "passive"))
    )
    (net (code "264") (name "unconnected-(SV4-Pad48)") (class "Default")
      (node (ref "SV4") (pin "48") (pinfunction "48_48") (pintype "passive"))
    )
    (net (code "265") (name "unconnected-(SV5-Pad3)") (class "Default")
      (node (ref "SV5") (pin "3") (pinfunction "3_3") (pintype "passive"))
    )
    (net (code "266") (name "unconnected-(SV5-Pad4)") (class "Default")
      (node (ref "SV5") (pin "4") (pinfunction "4_4") (pintype "passive"))
    )
    (net (code "267") (name "unconnected-(SV5-Pad5)") (class "Default")
      (node (ref "SV5") (pin "5") (pinfunction "5_5") (pintype "passive"))
    )
    (net (code "268") (name "unconnected-(SV5-Pad6)") (class "Default")
      (node (ref "SV5") (pin "6") (pinfunction "6_6") (pintype "passive"))
    )
    (net (code "269") (name "unconnected-(SV5-Pad7)") (class "Default")
      (node (ref "SV5") (pin "7") (pinfunction "7_7") (pintype "passive"))
    )
    (net (code "270") (name "unconnected-(SV5-Pad8)") (class "Default")
      (node (ref "SV5") (pin "8") (pinfunction "8_8") (pintype "passive"))
    )
    (net (code "271") (name "unconnected-(SV5-Pad9)") (class "Default")
      (node (ref "SV5") (pin "9") (pinfunction "9_9") (pintype "passive"))
    )
    (net (code "272") (name "unconnected-(SV5-Pad10)") (class "Default")
      (node (ref "SV5") (pin "10") (pinfunction "10_10") (pintype "passive"))
    )
    (net (code "273") (name "unconnected-(SV5-Pad11)") (class "Default")
      (node (ref "SV5") (pin "11") (pinfunction "11_11") (pintype "passive"))
    )
    (net (code "274") (name "unconnected-(SV5-Pad12)") (class "Default")
      (node (ref "SV5") (pin "12") (pinfunction "12_12") (pintype "passive"))
    )
    (net (code "275") (name "unconnected-(SV5-Pad13)") (class "Default")
      (node (ref "SV5") (pin "13") (pinfunction "13_13") (pintype "passive"))
    )
    (net (code "276") (name "unconnected-(SV5-Pad14)") (class "Default")
      (node (ref "SV5") (pin "14") (pinfunction "14_14") (pintype "passive"))
    )
    (net (code "277") (name "unconnected-(SV5-Pad15)") (class "Default")
      (node (ref "SV5") (pin "15") (pinfunction "15_15") (pintype "passive"))
    )
    (net (code "278") (name "unconnected-(SV5-Pad16)") (class "Default")
      (node (ref "SV5") (pin "16") (pinfunction "16_16") (pintype "passive"))
    )
    (net (code "279") (name "unconnected-(SV5-Pad17)") (class "Default")
      (node (ref "SV5") (pin "17") (pinfunction "17_17") (pintype "passive"))
    )
    (net (code "280") (name "unconnected-(SV5-Pad19)") (class "Default")
      (node (ref "SV5") (pin "19") (pinfunction "19_19") (pintype "passive"))
    )
    (net (code "281") (name "unconnected-(SV5-Pad20)") (class "Default")
      (node (ref "SV5") (pin "20") (pinfunction "20_20") (pintype "passive"))
    )
    (net (code "282") (name "unconnected-(SV5-Pad21)") (class "Default")
      (node (ref "SV5") (pin "21") (pinfunction "21_21") (pintype "passive"))
    )
    (net (code "283") (name "unconnected-(SV5-Pad23)") (class "Default")
      (node (ref "SV5") (pin "23") (pinfunction "23_23") (pintype "passive"))
    )
    (net (code "284") (name "unconnected-(SV5-Pad24)") (class "Default")
      (node (ref "SV5") (pin "24") (pinfunction "24_24") (pintype "passive"))
    )
    (net (code "285") (name "unconnected-(SV5-Pad25)") (class "Default")
      (node (ref "SV5") (pin "25") (pinfunction "25_25") (pintype "passive"))
    )
    (net (code "286") (name "unconnected-(SV5-Pad26)") (class "Default")
      (node (ref "SV5") (pin "26") (pinfunction "26_26") (pintype "passive"))
    )
    (net (code "287") (name "unconnected-(SV5-Pad27)") (class "Default")
      (node (ref "SV5") (pin "27") (pinfunction "27_27") (pintype "passive"))
    )
    (net (code "288") (name "unconnected-(SV5-Pad28)") (class "Default")
      (node (ref "SV5") (pin "28") (pinfunction "28_28") (pintype "passive"))
    )
    (net (code "289") (name "unconnected-(SV5-Pad29)") (class "Default")
      (node (ref "SV5") (pin "29") (pinfunction "29_29") (pintype "passive"))
    )
    (net (code "290") (name "unconnected-(SV5-Pad30)") (class "Default")
      (node (ref "SV5") (pin "30") (pinfunction "30_30") (pintype "passive"))
    )
    (net (code "291") (name "unconnected-(SV5-Pad31)") (class "Default")
      (node (ref "SV5") (pin "31") (pinfunction "31_31") (pintype "passive"))
    )
    (net (code "292") (name "unconnected-(SV5-Pad33)") (class "Default")
      (node (ref "SV5") (pin "33") (pinfunction "33_33") (pintype "passive"))
    )
    (net (code "293") (name "unconnected-(SV5-Pad35)") (class "Default")
      (node (ref "SV5") (pin "35") (pinfunction "35_35") (pintype "passive"))
    )
    (net (code "294") (name "unconnected-(SV5-Pad36)") (class "Default")
      (node (ref "SV5") (pin "36") (pinfunction "36_36") (pintype "passive"))
    )
    (net (code "295") (name "unconnected-(SV5-Pad38)") (class "Default")
      (node (ref "SV5") (pin "38") (pinfunction "38_38") (pintype "passive"))
    )
    (net (code "296") (name "unconnected-(SV5-Pad43)") (class "Default")
      (node (ref "SV5") (pin "43") (pinfunction "43_43") (pintype "passive"))
    )
    (net (code "297") (name "unconnected-(SV5-Pad44)") (class "Default")
      (node (ref "SV5") (pin "44") (pinfunction "44_44") (pintype "passive"))
    )
    (net (code "298") (name "unconnected-(SV5-Pad45)") (class "Default")
      (node (ref "SV5") (pin "45") (pinfunction "45_45") (pintype "passive"))
    )
    (net (code "299") (name "unconnected-(SV5-Pad46)") (class "Default")
      (node (ref "SV5") (pin "46") (pinfunction "46_46") (pintype "passive"))
    )
    (net (code "300") (name "unconnected-(SV5-Pad47)") (class "Default")
      (node (ref "SV5") (pin "47") (pinfunction "47_47") (pintype "passive"))
    )
    (net (code "301") (name "unconnected-(SV5-Pad48)") (class "Default")
      (node (ref "SV5") (pin "48") (pinfunction "48_48") (pintype "passive"))
    )
  )
)
